# microInv_batt_controller.net
KiCad netlist of a schematic drawn in Altium Designer
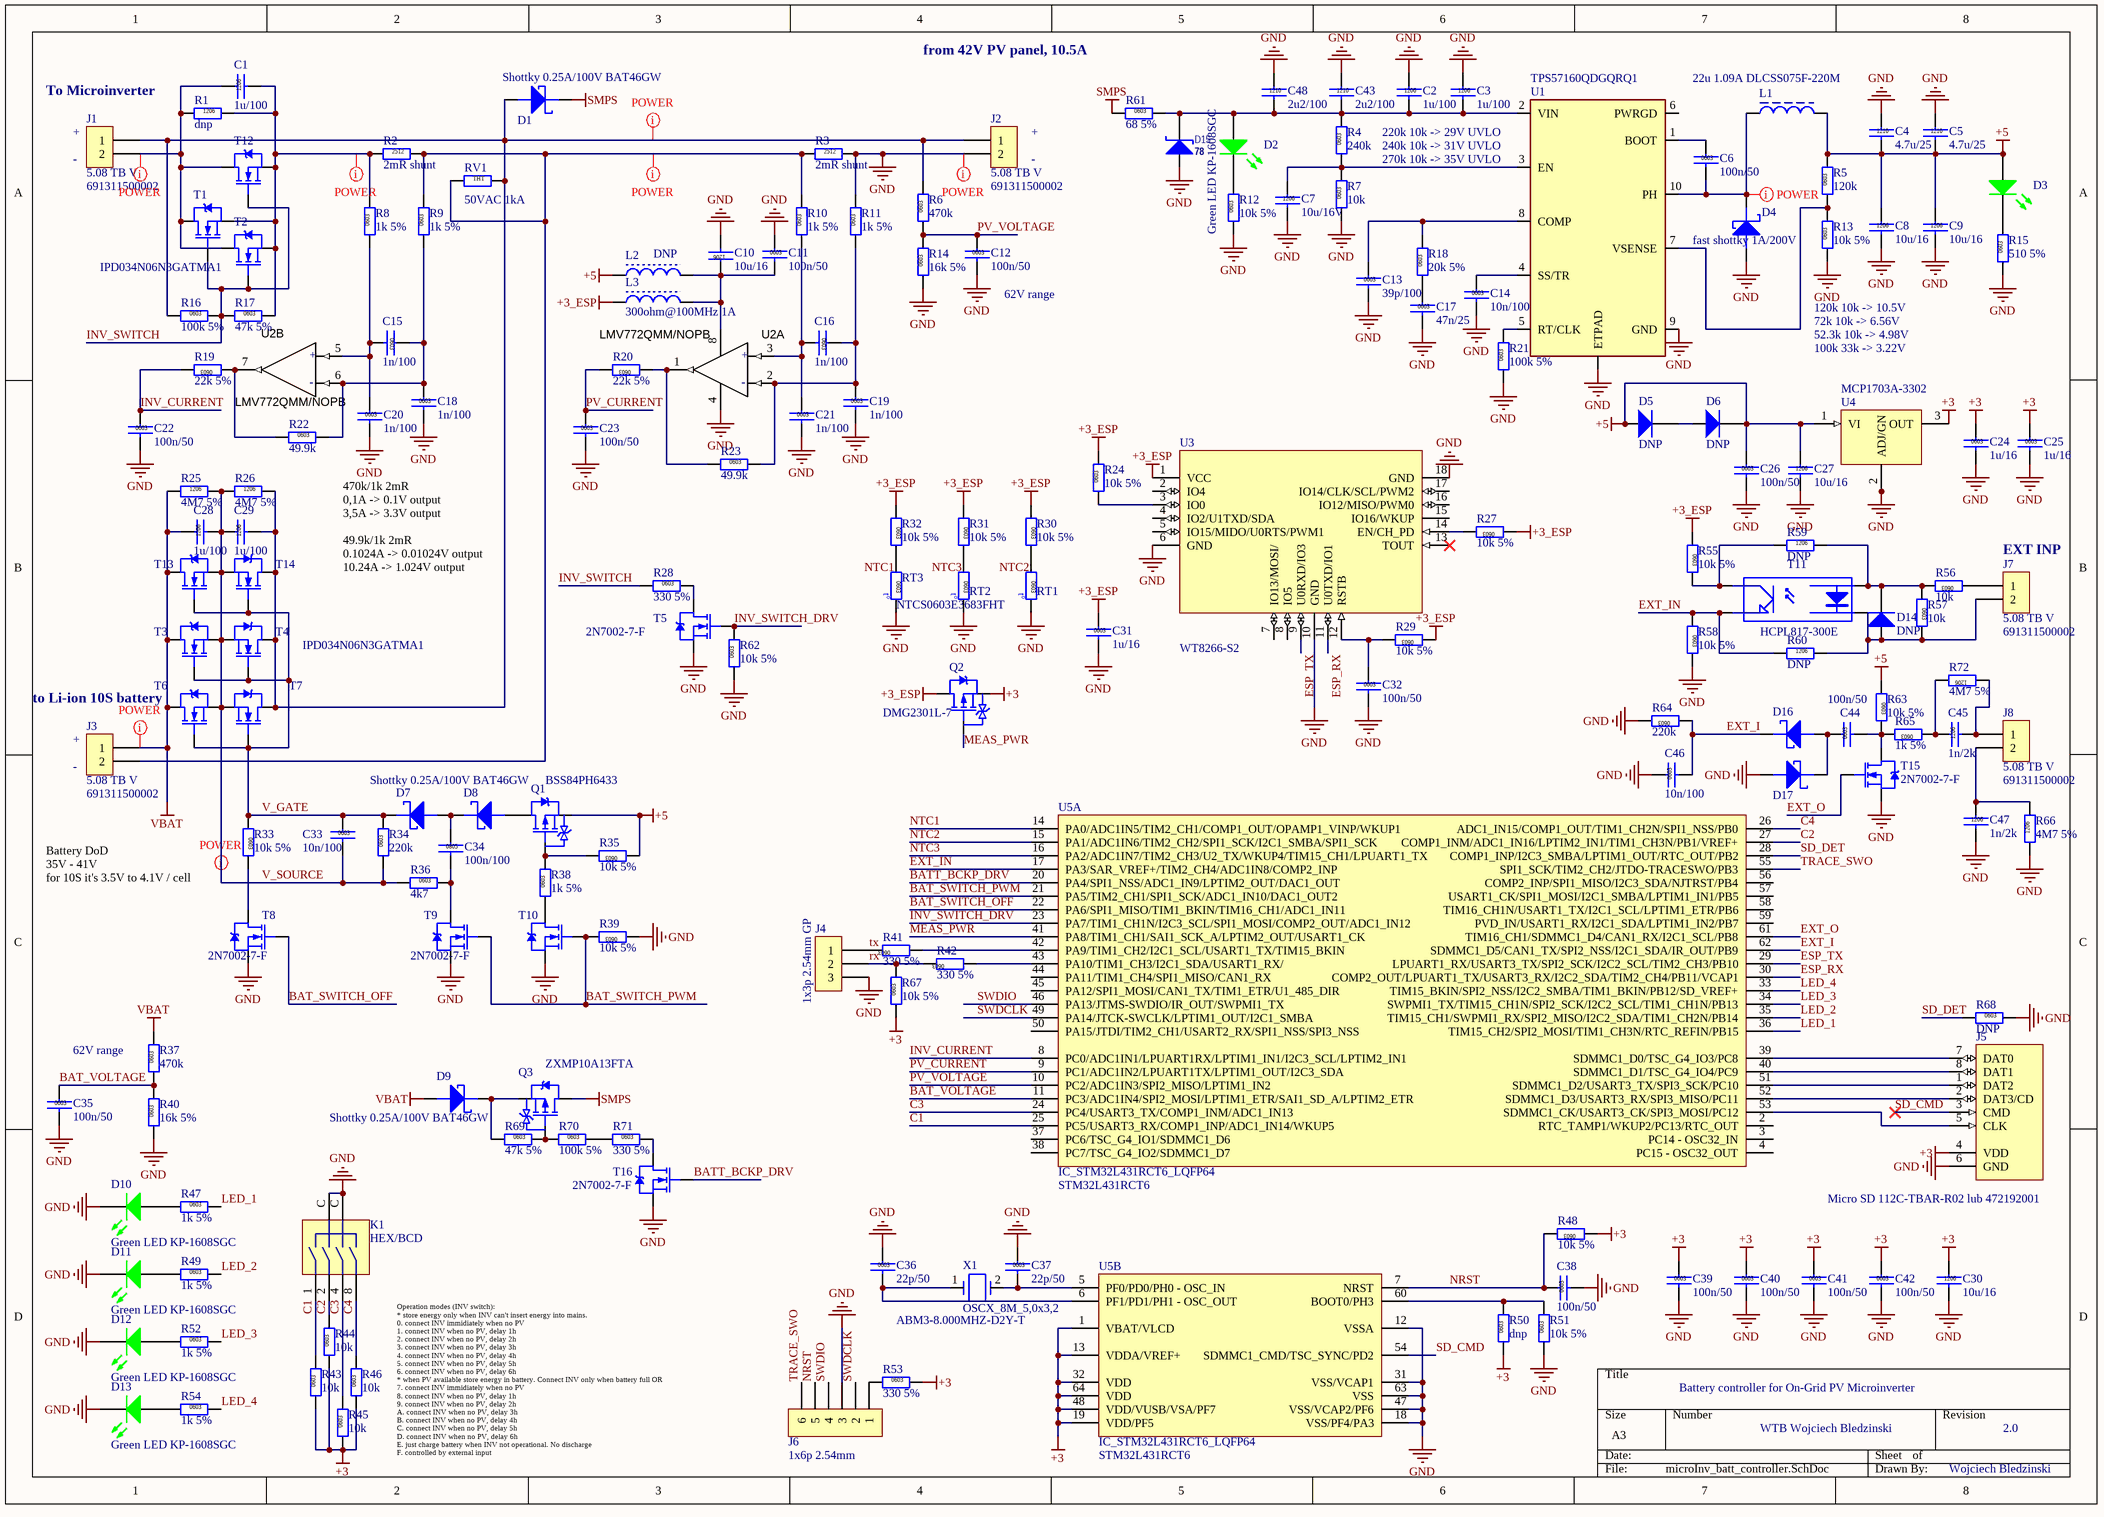
[diagram p0: microInv_batt_controller.SchDoc]

(export (version "E")
  (design (tool "Eeschema 10.0.6"))
  (components
    (comp (ref "C1")
      (value "1u/100")
      (footprint "CAP_1206")
      (description "X7R chip capacitor")
      (fields (field (name "MANUFACTURER") "AVX") (field (name "MANUFACTURER PART NUMBER") "12061C105KAT2A"))
      (libsource (lib "WB") (part "CAP_B_1u_100_1206_X7R"))
    )
    (comp (ref "C2")
      (value "1u/100")
      (footprint "CAP_1206")
      (description "X7R chip capacitor")
      (fields (field (name "MANUFACTURER") "AVX") (field (name "MANUFACTURER PART NUMBER") "12061C105KAT2A"))
      (libsource (lib "WB") (part "CAP_B_1u_100_1206_X7R"))
    )
    (comp (ref "C3")
      (value "1u/100")
      (footprint "CAP_1206")
      (description "X7R chip capacitor")
      (fields (field (name "MANUFACTURER") "AVX") (field (name "MANUFACTURER PART NUMBER") "12061C105KAT2A"))
      (libsource (lib "WB") (part "CAP_B_1u_100_1206_X7R"))
    )
    (comp (ref "C4")
      (value "4.7u/25")
      (footprint "CAP_1210")
      (description "X5R chip capacitor")
      (fields
        (field (name "MANUFACTURER") "YAGEO")
        (field (name "MANUFACTURER PART NUMBER") "CC1210KKX5R8BB475")
      )
      (libsource (lib "WB") (part "CAP_B_4.7u_25_1210_X5R"))
    )
    (comp (ref "C5")
      (value "4.7u/25")
      (footprint "CAP_1210")
      (description "X5R chip capacitor")
      (fields
        (field (name "MANUFACTURER") "YAGEO")
        (field (name "MANUFACTURER PART NUMBER") "CC1210KKX5R8BB475")
      )
      (libsource (lib "WB") (part "CAP_B_4.7u_25_1210_X5R"))
    )
    (comp (ref "C6")
      (value "100n/50")
      (footprint "CAP_0603")
      (description "X7R chip capacitor")
      (fields
        (field (name "MANUFACTURER") "SAMSUNG")
        (field (name "MANUFACTURER PART NUMBER") "CL10B104KB8NNNC")
      )
      (libsource (lib "WB") (part "CAP_B_100n_50_0603_X7R"))
    )
    (comp (ref "C7")
      (value "10u/16V")
      (footprint "CAP_1206")
      (description "X5R chip capacitor")
      (fields
        (field (name "MANUFACTURER") "SAMSUNG")
        (field (name "MANUFACTURER PART NUMBER") "CL31A106KAHNNNE")
      )
      (libsource (lib "WB") (part "CAP_B_10u_25_1206_X5R"))
    )
    (comp (ref "C8")
      (value "10u/16")
      (footprint "CAP_1206")
      (description "X7R chip capacitor")
      (fields
        (field (name "MANUFACTURER") "KYOCERA")
        (field (name "MANUFACTURER PART NUMBER") "CM316X7R106K16AT")
      )
      (libsource (lib "WB") (part "CAP_B_10u_16_1206_X7R"))
    )
    (comp (ref "C9")
      (value "10u/16")
      (footprint "CAP_1206")
      (description "X7R chip capacitor")
      (fields
        (field (name "MANUFACTURER") "KYOCERA")
        (field (name "MANUFACTURER PART NUMBER") "CM316X7R106K16AT")
      )
      (libsource (lib "WB") (part "CAP_B_10u_16_1206_X7R"))
    )
    (comp (ref "C10")
      (value "10u/16")
      (footprint "CAP_1206")
      (description "X7R chip capacitor")
      (fields
        (field (name "MANUFACTURER") "KYOCERA")
        (field (name "MANUFACTURER PART NUMBER") "CM316X7R106K16AT")
      )
      (libsource (lib "WB") (part "CAP_B_10u_16_1206_X7R"))
    )
    (comp (ref "C11")
      (value "100n/50")
      (footprint "CAP_0603")
      (description "X7R chip capacitor")
      (fields
        (field (name "MANUFACTURER") "SAMSUNG")
        (field (name "MANUFACTURER PART NUMBER") "CL10B104KB8NNNC")
      )
      (libsource (lib "WB") (part "CAP_B_100n_50_0603_X7R"))
    )
    (comp (ref "C12")
      (value "100n/50")
      (footprint "CAP_0603")
      (description "X7R chip capacitor")
      (fields
        (field (name "MANUFACTURER") "SAMSUNG")
        (field (name "MANUFACTURER PART NUMBER") "CL10B104KB8NNNC")
      )
      (libsource (lib "WB") (part "CAP_B_100n_50_0603_X7R"))
    )
    (comp (ref "C13")
      (value "39p/100")
      (footprint "CAP_0603")
      (description "COG chip capacitor")
      (fields (field (name "TOLERANCE") "10%") (field (name "VOLTAGE") "100"))
      (libsource (lib "WB") (part "CAP_B_39p_100_0603_COG"))
    )
    (comp (ref "C14")
      (value "10n/100")
      (footprint "CAP_0603")
      (description "X7R chip capacitor")
      (fields
        (field (name "MANUFACTURER") "SAMSUNG")
        (field (name "MANUFACTURER PART NUMBER") "CL10B103KC8NNNC")
      )
      (libsource (lib "WB") (part "CAP_B_10n_100_0603_X7R"))
    )
    (comp (ref "C15")
      (value "1n/100")
      (footprint "CAP_0603")
      (description "X7R chip capacitor")
      (fields
        (field (name "MANUFACTURER") "SAMSUNG")
        (field (name "MANUFACTURER PART NUMBER") "CL10B102KC8NNNC")
      )
      (libsource (lib "WB") (part "CAP_B_1n_100_0603_X7R"))
    )
    (comp (ref "C16")
      (value "1n/100")
      (footprint "CAP_0603")
      (description "X7R chip capacitor")
      (fields
        (field (name "MANUFACTURER") "SAMSUNG")
        (field (name "MANUFACTURER PART NUMBER") "CL10B102KC8NNNC")
      )
      (libsource (lib "WB") (part "CAP_B_1n_100_0603_X7R"))
    )
    (comp (ref "C17")
      (value "47n/25")
      (footprint "CAP_0603")
      (description "X7R chip capacitor")
      (fields (field (name "TOLERANCE") "10%") (field (name "VOLTAGE") "25"))
      (libsource (lib "WB") (part "CAP_B_47n_25_0603_X7R"))
    )
    (comp (ref "C18")
      (value "1n/100")
      (footprint "CAP_0603")
      (description "X7R chip capacitor")
      (fields
        (field (name "MANUFACTURER") "SAMSUNG")
        (field (name "MANUFACTURER PART NUMBER") "CL10B102KC8NNNC")
      )
      (libsource (lib "WB") (part "CAP_B_1n_100_0603_X7R"))
    )
    (comp (ref "C19")
      (value "1n/100")
      (footprint "CAP_0603")
      (description "X7R chip capacitor")
      (fields
        (field (name "MANUFACTURER") "SAMSUNG")
        (field (name "MANUFACTURER PART NUMBER") "CL10B102KC8NNNC")
      )
      (libsource (lib "WB") (part "CAP_B_1n_100_0603_X7R"))
    )
    (comp (ref "C20")
      (value "1n/100")
      (footprint "CAP_0603")
      (description "X7R chip capacitor")
      (fields
        (field (name "MANUFACTURER") "SAMSUNG")
        (field (name "MANUFACTURER PART NUMBER") "CL10B102KC8NNNC")
      )
      (libsource (lib "WB") (part "CAP_B_1n_100_0603_X7R"))
    )
    (comp (ref "C21")
      (value "1n/100")
      (footprint "CAP_0603")
      (description "X7R chip capacitor")
      (fields
        (field (name "MANUFACTURER") "SAMSUNG")
        (field (name "MANUFACTURER PART NUMBER") "CL10B102KC8NNNC")
      )
      (libsource (lib "WB") (part "CAP_B_1n_100_0603_X7R"))
    )
    (comp (ref "C22")
      (value "100n/50")
      (footprint "CAP_0603")
      (description "X7R chip capacitor")
      (fields
        (field (name "MANUFACTURER") "SAMSUNG")
        (field (name "MANUFACTURER PART NUMBER") "CL10B104KB8NNNC")
      )
      (libsource (lib "WB") (part "CAP_B_100n_50_0603_X7R"))
    )
    (comp (ref "C23")
      (value "100n/50")
      (footprint "CAP_0603")
      (description "X7R chip capacitor")
      (fields
        (field (name "MANUFACTURER") "SAMSUNG")
        (field (name "MANUFACTURER PART NUMBER") "CL10B104KB8NNNC")
      )
      (libsource (lib "WB") (part "CAP_B_100n_50_0603_X7R"))
    )
    (comp (ref "C24")
      (value "1u/16")
      (footprint "CAP_0603")
      (description "X7R chip capacitor")
      (fields
        (field (name "MANUFACTURER") "SAMSUNG")
        (field (name "MANUFACTURER PART NUMBER") "CL10B105KO8NNNC")
      )
      (libsource (lib "WB") (part "CAP_B_1u_16_0603_X7R"))
    )
    (comp (ref "C25")
      (value "1u/16")
      (footprint "CAP_0603")
      (description "X7R chip capacitor")
      (fields
        (field (name "MANUFACTURER") "SAMSUNG")
        (field (name "MANUFACTURER PART NUMBER") "CL10B105KO8NNNC")
      )
      (libsource (lib "WB") (part "CAP_B_1u_16_0603_X7R"))
    )
    (comp (ref "C26")
      (value "100n/50")
      (footprint "CAP_0603")
      (description "X7R chip capacitor")
      (fields
        (field (name "MANUFACTURER") "SAMSUNG")
        (field (name "MANUFACTURER PART NUMBER") "CL10B104KB8NNNC")
      )
      (libsource (lib "WB") (part "CAP_B_100n_50_0603_X7R"))
    )
    (comp (ref "C27")
      (value "10u/16")
      (footprint "CAP_1206")
      (description "X7R chip capacitor")
      (fields
        (field (name "MANUFACTURER") "KYOCERA")
        (field (name "MANUFACTURER PART NUMBER") "CM316X7R106K16AT")
      )
      (libsource (lib "WB") (part "CAP_B_10u_16_1206_X7R"))
    )
    (comp (ref "C28")
      (value "1u/100")
      (footprint "CAP_1206")
      (description "X7R chip capacitor")
      (fields (field (name "MANUFACTURER") "AVX") (field (name "MANUFACTURER PART NUMBER") "12061C105KAT2A"))
      (libsource (lib "WB") (part "CAP_B_1u_100_1206_X7R"))
    )
    (comp (ref "C29")
      (value "1u/100")
      (footprint "CAP_1206")
      (description "X7R chip capacitor")
      (fields (field (name "MANUFACTURER") "AVX") (field (name "MANUFACTURER PART NUMBER") "12061C105KAT2A"))
      (libsource (lib "WB") (part "CAP_B_1u_100_1206_X7R"))
    )
    (comp (ref "C30")
      (value "10u/16")
      (footprint "CAP_1206")
      (description "X7R chip capacitor")
      (fields
        (field (name "MANUFACTURER") "KYOCERA")
        (field (name "MANUFACTURER PART NUMBER") "CM316X7R106K16AT")
      )
      (libsource (lib "WB") (part "CAP_B_10u_16_1206_X7R"))
    )
    (comp (ref "C31")
      (value "1u/16")
      (footprint "CAP_0603")
      (description "X7R chip capacitor")
      (fields
        (field (name "MANUFACTURER") "SAMSUNG")
        (field (name "MANUFACTURER PART NUMBER") "CL10B105KO8NNNC")
      )
      (libsource (lib "WB") (part "CAP_B_1u_16_0603_X7R"))
    )
    (comp (ref "C32")
      (value "100n/50")
      (footprint "CAP_0603")
      (description "X7R chip capacitor")
      (fields
        (field (name "MANUFACTURER") "SAMSUNG")
        (field (name "MANUFACTURER PART NUMBER") "CL10B104KB8NNNC")
      )
      (libsource (lib "WB") (part "CAP_B_100n_50_0603_X7R"))
    )
    (comp (ref "C33")
      (value "10n/100")
      (footprint "CAP_0603")
      (description "X7R chip capacitor")
      (fields
        (field (name "MANUFACTURER") "SAMSUNG")
        (field (name "MANUFACTURER PART NUMBER") "CL10B103KC8NNNC")
      )
      (libsource (lib "WB") (part "CAP_B_10n_100_0603_X7R"))
    )
    (comp (ref "C34")
      (value "100n/100")
      (footprint "CAP_0805")
      (description "X7R chip capacitor")
      (fields (field (name "MANUFACTURER") "AVX") (field (name "MANUFACTURER PART NUMBER") "08051C104KAZ2A"))
      (libsource (lib "WB") (part "CAP_B_100n_100_0805_X7R"))
    )
    (comp (ref "C35")
      (value "100n/50")
      (footprint "CAP_0603")
      (description "X7R chip capacitor")
      (fields
        (field (name "MANUFACTURER") "SAMSUNG")
        (field (name "MANUFACTURER PART NUMBER") "CL10B104KB8NNNC")
      )
      (libsource (lib "WB") (part "CAP_B_100n_50_0603_X7R"))
    )
    (comp (ref "C36")
      (value "22p/50")
      (footprint "CAP_0603")
      (description "X7R chip capacitor")
      (fields (field (name "TOLERANCE") "10%") (field (name "VOLTAGE") "50"))
      (libsource (lib "WB") (part "CAP_B_22p_50_0603_X7R"))
    )
    (comp (ref "C37")
      (value "22p/50")
      (footprint "CAP_0603")
      (description "X7R chip capacitor")
      (fields (field (name "TOLERANCE") "10%") (field (name "VOLTAGE") "50"))
      (libsource (lib "WB") (part "CAP_B_22p_50_0603_X7R"))
    )
    (comp (ref "C38")
      (value "100n/50")
      (footprint "CAP_0603")
      (description "X7R chip capacitor")
      (fields
        (field (name "MANUFACTURER") "SAMSUNG")
        (field (name "MANUFACTURER PART NUMBER") "CL10B104KB8NNNC")
      )
      (libsource (lib "WB") (part "CAP_B_100n_50_0603_X7R"))
    )
    (comp (ref "C39")
      (value "100n/50")
      (footprint "CAP_0603")
      (description "X7R chip capacitor")
      (fields
        (field (name "MANUFACTURER") "SAMSUNG")
        (field (name "MANUFACTURER PART NUMBER") "CL10B104KB8NNNC")
      )
      (libsource (lib "WB") (part "CAP_B_100n_50_0603_X7R"))
    )
    (comp (ref "C40")
      (value "100n/50")
      (footprint "CAP_0603")
      (description "X7R chip capacitor")
      (fields
        (field (name "MANUFACTURER") "SAMSUNG")
        (field (name "MANUFACTURER PART NUMBER") "CL10B104KB8NNNC")
      )
      (libsource (lib "WB") (part "CAP_B_100n_50_0603_X7R"))
    )
    (comp (ref "C41")
      (value "100n/50")
      (footprint "CAP_0603")
      (description "X7R chip capacitor")
      (fields
        (field (name "MANUFACTURER") "SAMSUNG")
        (field (name "MANUFACTURER PART NUMBER") "CL10B104KB8NNNC")
      )
      (libsource (lib "WB") (part "CAP_B_100n_50_0603_X7R"))
    )
    (comp (ref "C42")
      (value "100n/50")
      (footprint "CAP_0603")
      (description "X7R chip capacitor")
      (fields
        (field (name "MANUFACTURER") "SAMSUNG")
        (field (name "MANUFACTURER PART NUMBER") "CL10B104KB8NNNC")
      )
      (libsource (lib "WB") (part "CAP_B_100n_50_0603_X7R"))
    )
    (comp (ref "C43")
      (value "2u2/100")
      (footprint "CAP_1210")
      (description "X7R chip capacitor")
      (fields
        (field (name "MANUFACTURER") "KEMET")
        (field (name "MANUFACTURER PART NUMBER") "C1210C225M1RACTU")
      )
      (libsource (lib "WB") (part "CAP_B_2u2_100_1210_X7R"))
    )
    (comp (ref "C44")
      (value "100n/50")
      (footprint "CAP_0603")
      (description "X7R chip capacitor")
      (fields
        (field (name "MANUFACTURER") "SAMSUNG")
        (field (name "MANUFACTURER PART NUMBER") "CL10B104KB8NNNC")
      )
      (libsource (lib "WB") (part "CAP_B_100n_50_0603_X7R"))
    )
    (comp (ref "C45")
      (value "1n/2k")
      (footprint "CAP_1206")
      (description "X7R chip capacitor")
      (fields
        (field (name "MANUFACTURER") "MULTICOMP")
        (field (name "MANUFACTURER PART NUMBER") "MC1206B102K202CT")
      )
      (libsource (lib "WB") (part "CAP_B_1n_2k_1206_X7R"))
    )
    (comp (ref "C46")
      (value "10n/100")
      (footprint "CAP_0603")
      (description "X7R chip capacitor")
      (fields
        (field (name "MANUFACTURER") "SAMSUNG")
        (field (name "MANUFACTURER PART NUMBER") "CL10B103KC8NNNC")
      )
      (libsource (lib "WB") (part "CAP_B_10n_100_0603_X7R"))
    )
    (comp (ref "C47")
      (value "1n/2k")
      (footprint "CAP_1206")
      (description "X7R chip capacitor")
      (fields
        (field (name "MANUFACTURER") "MULTICOMP")
        (field (name "MANUFACTURER PART NUMBER") "MC1206B102K202CT")
      )
      (libsource (lib "WB") (part "CAP_B_1n_2k_1206_X7R"))
    )
    (comp (ref "C48")
      (value "2u2/100")
      (footprint "CAP_1210")
      (description "X7R chip capacitor")
      (fields
        (field (name "MANUFACTURER") "KEMET")
        (field (name "MANUFACTURER PART NUMBER") "C1210C225M1RACTU")
      )
      (libsource (lib "WB") (part "CAP_B_2u2_100_1210_X7R"))
    )
    (comp (ref "D1")
      (value "Shottky 0.25A/100V BAT46GW")
      (footprint "SOD_123")
      (description "Shottky Diode trr 4ns 0,43V @ 0.05A 0.75V@0.25A")
      (fields
        (field (name "MANUFACTURER") "Nexperia")
        (field (name "MANUFACTURER PART NUMBER") "BAT46GWX 934070363115")
      )
      (libsource (lib "WB") (part "D_0.25_100_BAT46GWX"))
    )
    (comp (ref "D2")
      (value "Green LED KP-1608SGC")
      (footprint "LED_0603_GREEN")
      (description "Diode LED SMD 2.2V @ 20mA 15mcd")
      (fields
        (field (name "MANUFACTURER") "KINGBRIGHT")
        (field (name "MANUFACTURER PART NUMBER") "KP-1608SGC")
      )
      (libsource (lib "WB") (part "D_LED_0603_GREEN"))
    )
    (comp (ref "D3")
      (value "Green LED KP-1608SGC")
      (footprint "LED_0603_GREEN")
      (description "Diode LED SMD 2.2V @ 20mA 15mcd")
      (fields
        (field (name "MANUFACTURER") "KINGBRIGHT")
        (field (name "MANUFACTURER PART NUMBER") "KP-1608SGC")
      )
      (libsource (lib "WB") (part "D_LED_0603_GREEN"))
    )
    (comp (ref "D4")
      (value "fast shottky 1A/200V")
      (footprint "SMA_DO-214AC")
      (description "Shottky Diode 0,9V @ 1A trr=15ns 7pF")
      (fields (field (name "MANUFACTURER") "FAIRCHILD") (field (name "MANUFACTURER PART NUMBER") "ES1D"))
      (libsource (lib "WB") (part "D_1A_200_ES1D"))
    )
    (comp (ref "D5")
      (value "DNP")
      (footprint "D_MINIMELF")
      (fields
        (field (name "MANUFACTURER") "ON SEMICONDUCTOR (FAIRCHILD)")
        (field (name "MANUFACTURER PART NUMBER") "FDLL4148")
      )
      (libsource (lib "WB") (part "D_LL4148_MMELF"))
    )
    (comp (ref "D6")
      (value "DNP")
      (footprint "D_MINIMELF")
      (fields
        (field (name "MANUFACTURER") "ON SEMICONDUCTOR (FAIRCHILD)")
        (field (name "MANUFACTURER PART NUMBER") "FDLL4148")
      )
      (libsource (lib "WB") (part "D_LL4148_MMELF"))
    )
    (comp (ref "D7")
      (value "Shottky 0.25A/100V BAT46GW")
      (footprint "SOD_123")
      (description "Shottky Diode trr 4ns 0,43V @ 0.05A 0.75V@0.25A")
      (fields
        (field (name "MANUFACTURER") "Nexperia")
        (field (name "MANUFACTURER PART NUMBER") "BAT46GWX 934070363115")
      )
      (libsource (lib "WB") (part "D_0.25_100_BAT46GWX"))
    )
    (comp (ref "D8")
      (value "Shottky 0.25A/100V BAT46GW")
      (footprint "SOD_123")
      (description "Shottky Diode trr 4ns 0,43V @ 0.05A 0.75V@0.25A")
      (fields
        (field (name "MANUFACTURER") "Nexperia")
        (field (name "MANUFACTURER PART NUMBER") "BAT46GWX 934070363115")
      )
      (libsource (lib "WB") (part "D_0.25_100_BAT46GWX"))
    )
    (comp (ref "D9")
      (value "Shottky 0.25A/100V BAT46GW")
      (footprint "SOD_123")
      (description "Shottky Diode trr 4ns 0,43V @ 0.05A 0.75V@0.25A")
      (fields
        (field (name "MANUFACTURER") "Nexperia")
        (field (name "MANUFACTURER PART NUMBER") "BAT46GWX 934070363115")
      )
      (libsource (lib "WB") (part "D_0.25_100_BAT46GWX"))
    )
    (comp (ref "D10")
      (value "Green LED KP-1608SGC")
      (footprint "LED_0603_GREEN")
      (description "Diode LED SMD 2.2V @ 20mA 15mcd")
      (fields
        (field (name "MANUFACTURER") "KINGBRIGHT")
        (field (name "MANUFACTURER PART NUMBER") "KP-1608SGC")
      )
      (libsource (lib "WB") (part "D_LED_0603_GREEN"))
    )
    (comp (ref "D11")
      (value "Green LED KP-1608SGC")
      (footprint "LED_0603_GREEN")
      (description "Diode LED SMD 2.2V @ 20mA 15mcd")
      (fields
        (field (name "MANUFACTURER") "KINGBRIGHT")
        (field (name "MANUFACTURER PART NUMBER") "KP-1608SGC")
      )
      (libsource (lib "WB") (part "D_LED_0603_GREEN"))
    )
    (comp (ref "D12")
      (value "Green LED KP-1608SGC")
      (footprint "LED_0603_GREEN")
      (description "Diode LED SMD 2.2V @ 20mA 15mcd")
      (fields
        (field (name "MANUFACTURER") "KINGBRIGHT")
        (field (name "MANUFACTURER PART NUMBER") "KP-1608SGC")
      )
      (libsource (lib "WB") (part "D_LED_0603_GREEN"))
    )
    (comp (ref "D13")
      (value "Green LED KP-1608SGC")
      (footprint "LED_0603_GREEN")
      (description "Diode LED SMD 2.2V @ 20mA 15mcd")
      (fields
        (field (name "MANUFACTURER") "KINGBRIGHT")
        (field (name "MANUFACTURER PART NUMBER") "KP-1608SGC")
      )
      (libsource (lib "WB") (part "D_LED_0603_GREEN"))
    )
    (comp (ref "D14")
      (value "DNP")
      (footprint "D_MINIMELF")
      (fields
        (field (name "MANUFACTURER") "ON SEMICONDUCTOR (FAIRCHILD)")
        (field (name "MANUFACTURER PART NUMBER") "FDLL4148")
      )
      (libsource (lib "WB") (part "D_LL4148_MMELF"))
    )
    (comp (ref "D15")
      (value "78")
      (footprint "SMA_DO-214AC")
      (description "transil jednostronny 400W")
      (fields (field (name "MANUFACTURER") "MULTICOMP") (field (name "MANUFACTURER PART NUMBER") "SMAJ78A"))
      (libsource (lib "WB") (part "D_TR_UNI_SMAJ78A"))
    )
    (comp (ref "D16")
      (value "Shottky 0.25A/100V BAT46GW")
      (footprint "SOD_123")
      (description "Shottky Diode trr 4ns 0,43V @ 0.05A 0.75V@0.25A")
      (fields
        (field (name "MANUFACTURER") "Nexperia")
        (field (name "MANUFACTURER PART NUMBER") "BAT46GWX 934070363115")
      )
      (libsource (lib "WB") (part "D_0.25_100_BAT46GWX"))
    )
    (comp (ref "D17")
      (value "Shottky 0.25A/100V BAT46GW")
      (footprint "SOD_123")
      (description "Shottky Diode trr 4ns 0,43V @ 0.05A 0.75V@0.25A")
      (fields
        (field (name "MANUFACTURER") "Nexperia")
        (field (name "MANUFACTURER PART NUMBER") "BAT46GWX 934070363115")
      )
      (libsource (lib "WB") (part "D_0.25_100_BAT46GWX"))
    )
    (comp (ref "J1")
      (value "5.08 TB V")
      (footprint "CON_1x2_5.08TB")
      (description "THT 5,08mm, WE 691311500002 (rev1), NINIGI , MLX")
      (fields
        (field (name "MANUFACTURER") "Wurth Electronics")
        (field (name "MANUFACTURER PART NUMBER") "691311500002")
      )
      (libsource (lib "WB") (part "CON_1x2_TB_5.08V"))
    )
    (comp (ref "J2")
      (value "5.08 TB V")
      (footprint "CON_1x2_5.08TB")
      (description "THT 5,08mm, WE 691311500002 (rev1), NINIGI , MLX")
      (fields
        (field (name "MANUFACTURER") "Wurth Electronics")
        (field (name "MANUFACTURER PART NUMBER") "691311500002")
      )
      (libsource (lib "") (part "CON_1x2_TB_5.08V_1"))
    )
    (comp (ref "J3")
      (value "5.08 TB V")
      (footprint "CON_1x2_5.08TB")
      (description "THT 5,08mm, WE 691311500002 (rev1), NINIGI , MLX")
      (fields
        (field (name "MANUFACTURER") "Wurth Electronics")
        (field (name "MANUFACTURER PART NUMBER") "691311500002")
      )
      (libsource (lib "WB") (part "CON_1x2_TB_5.08V"))
    )
    (comp (ref "J4")
      (value "1x3p 2.54mm GP")
      (footprint "CON_PIN1x3_THT")
      (description "THT 2,54 goldpin")
      (fields (field (name "MANUFACTURER") "TME") (field (name "MANUFACTURER PART NUMBER") "ZL201-03G"))
      (libsource (lib "WB") (part "CON_1x3_GP_THT"))
    )
    (comp (ref "J5")
      (value "Micro SD 112C-TBAR-R02 lub 472192001")
      (footprint "112C_TXAR_R01")
      (description "Micro SD connector SMD, ATTEND 112C-TBAR-R02; MOLEX 472192001")
      (fields
        (field (name "MANUFACTURER") "ATTEND")
        (field (name "MANUFACTURER PART NUMBER") "112C-TBAR-R02")
      )
      (libsource (lib "WB") (part "CON_MicroSD"))
    )
    (comp (ref "J6")
      (value "1x6p 2.54mm")
      (footprint "CON_PIN1x6_THT")
      (description "THT 2,54 goldpin")
      (fields
        (field (name "MANUFACTURER") "CONNFLY")
        (field (name "MANUFACTURER PART NUMBER") "DS1021-1*6SF1-1")
      )
      (libsource (lib "WB") (part "CON_1x6_GP_THT"))
    )
    (comp (ref "J7")
      (value "5.08 TB V")
      (footprint "CON_1x2_5.08TB")
      (description "THT 5,08mm, WE 691311500002 (rev1), NINIGI , MLX")
      (fields
        (field (name "MANUFACTURER") "Wurth Electronics")
        (field (name "MANUFACTURER PART NUMBER") "691311500002")
      )
      (libsource (lib "") (part "CON_1x2_TB_5.08V_1"))
    )
    (comp (ref "J8")
      (value "5.08 TB V")
      (footprint "CON_1x2_5.08TB")
      (description "THT 5,08mm, WE 691311500002 (rev1), NINIGI , MLX")
      (fields
        (field (name "MANUFACTURER") "Wurth Electronics")
        (field (name "MANUFACTURER PART NUMBER") "691311500002")
      )
      (libsource (lib "") (part "CON_1x2_TB_5.08V_1"))
    )
    (comp (ref "K1")
      (value "HEX/BCD")
      (footprint "MECH_SW_HEXBCD")
      (description "Zadajnik kodu")
      (fields (field (name "MANUFACTURER") "ECE") (field (name "MANUFACTURER PART NUMBER") "ERD116RSZ"))
      (libsource (lib "WB") (part "MECH_SW_HEXBCD"))
    )
    (comp (ref "L1")
      (value "22u 1.09A DLCSS075F-220M")
      (footprint "IND_DER0705")
      (description "shielded power inductor 1.09A Rdc=0,12")
      (fields
        (field (name "MANUFACTURER") "FERROCORE")
        (field (name "MANUFACTURER PART NUMBER") "DER0705-22")
      )
      (libsource (lib "WB") (part "IND_22u_1.09A_DER0705-22"))
    )
    (comp (ref "L2")
      (value "DNP")
      (footprint "RES_0603")
      (description "2A Rdc=0,15 SRF 250MHz")
      (fields (field (name "MANUFACTURER") "WE") (field (name "MANUFACTURER PART NUMBER") "742792641"))
      (libsource (lib "WB") (part "IND_FB_300R_0603"))
    )
    (comp (ref "L3")
      (value "300ohm@100MHz 1A")
      (footprint "RES_0603")
      (description "2A Rdc=0,15 SRF 250MHz")
      (fields (field (name "MANUFACTURER") "WE") (field (name "MANUFACTURER PART NUMBER") "742792641"))
      (libsource (lib "WB") (part "IND_FB_300R_0603"))
    )
    (comp (ref "Q1")
      (value "BSS84PH6433")
      (footprint "SOT23-3")
      (description "50V 130mA P Mosfet")
      (fields (field (name "MANUFACTURER") "INFINEON TECHNOLOGIES") (field (name "POWER") "360mW"))
      (libsource (lib "WB") (part "T_BSS84"))
    )
    (comp (ref "Q2")
      (value "DMG2301L-7")
      (footprint "SOT23-3")
      (description "20V 3A P Mosfet")
      (fields (field (name "MANUFACTURER") "DIODES"))
      (libsource (lib "WB") (part "T_DMG2301L-7"))
    )
    (comp (ref "Q3")
      (value "ZXMP10A13FTA")
      (footprint "SOT23-3")
      (description "100V 700mA P Mosfet")
      (fields (field (name "MANUFACTURER") "DIODES"))
      (libsource (lib "WB") (part "T_ZXMP10A13FTA"))
    )
    (comp (ref "R1")
      (value "dnp")
      (footprint "RES_1206")
      (description "Resistor 1206 5% 0,25W")
      (fields
        (field (name "MANUFACTURER") "ROYAL OHM")
        (field (name "MANUFACTURER PART NUMBER") "1206S4J0000T5E")
      )
      (libsource (lib "WB") (part "RES_0R_5p_1206"))
    )
    (comp (ref "R2")
      (value "2mR shunt")
      (footprint "RES_2512_shunt")
      (description "Resistor 2512 5% 1W")
      (fields (field (name "MANUFACTURER") "YAGEO") (field (name "TOLERANCE") "5%"))
      (libsource (lib "WB") (part "RES_2mR_1p_2512"))
    )
    (comp (ref "R3")
      (value "2mR shunt")
      (footprint "RES_2512_shunt")
      (description "Resistor 2512 5% 1W")
      (fields (field (name "MANUFACTURER") "YAGEO") (field (name "TOLERANCE") "5%"))
      (libsource (lib "WB") (part "RES_2mR_1p_2512"))
    )
    (comp (ref "R4")
      (value "240k")
      (footprint "RES_0603")
      (description "Resistor 0603 5% 0,1W")
      (fields (field (name "TOLERANCE") "5%") (field (name "VOLTAGE") "50"))
      (libsource (lib "WB") (part "RES_105k_5p_0603"))
    )
    (comp (ref "R5")
      (value "120k")
      (footprint "RES_0603")
      (description "Resistor 0603 5% 0,1W")
      (fields (field (name "MANUFACTURER") "YAGEO") (field (name "TOLERANCE") "5%"))
      (libsource (lib "WB") (part "RES_62k_5p_0603"))
    )
    (comp (ref "R6")
      (value "470k")
      (footprint "RES_0603")
      (description "Resistor 0603 5% 0,1W")
      (fields (field (name "MANUFACTURER") "YAGEO") (field (name "TOLERANCE") "5%"))
      (libsource (lib "") (part "RES_1k_5p_0603_2"))
    )
    (comp (ref "R7")
      (value "10k")
      (footprint "RES_0603")
      (description "Resistor 0603 5% 0,1W")
      (fields (field (name "MANUFACTURER") "YAGEO") (field (name "TOLERANCE") "5%"))
      (libsource (lib "WB") (part "RES_16k_5p_0603"))
    )
    (comp (ref "R8")
      (value "1k 5%")
      (footprint "RES_0603")
      (description "Resistor 0603 5% 0,1W")
      (fields (field (name "MANUFACTURER") "YAGEO") (field (name "TOLERANCE") "5%"))
      (libsource (lib "") (part "RES_1k_5p_0603_2"))
    )
    (comp (ref "R9")
      (value "1k 5%")
      (footprint "RES_0603")
      (description "Resistor 0603 5% 0,1W")
      (fields (field (name "MANUFACTURER") "YAGEO") (field (name "TOLERANCE") "5%"))
      (libsource (lib "") (part "RES_1k_5p_0603_2"))
    )
    (comp (ref "R10")
      (value "1k 5%")
      (footprint "RES_0603")
      (description "Resistor 0603 5% 0,1W")
      (fields (field (name "MANUFACTURER") "YAGEO") (field (name "TOLERANCE") "5%"))
      (libsource (lib "") (part "RES_1k_5p_0603_2"))
    )
    (comp (ref "R11")
      (value "1k 5%")
      (footprint "RES_0603")
      (description "Resistor 0603 5% 0,1W")
      (fields (field (name "MANUFACTURER") "YAGEO") (field (name "TOLERANCE") "5%"))
      (libsource (lib "") (part "RES_1k_5p_0603_2"))
    )
    (comp (ref "R12")
      (value "10k 5%")
      (footprint "RES_0603")
      (description "Resistor 0603 5% 0,1W")
      (fields (field (name "TOLERANCE") "5%") (field (name "VOLTAGE") "50"))
      (libsource (lib "WB") (part "RES_10k_5p_0603"))
    )
    (comp (ref "R13")
      (value "10k 5%")
      (footprint "RES_0603")
      (description "Resistor 0603 5% 0,1W")
      (fields (field (name "TOLERANCE") "5%") (field (name "VOLTAGE") "50"))
      (libsource (lib "WB") (part "RES_10k_5p_0603"))
    )
    (comp (ref "R14")
      (value "16k 5%")
      (footprint "RES_0603")
      (description "Resistor 0603 5% 0,1W")
      (fields (field (name "MANUFACTURER") "YAGEO") (field (name "TOLERANCE") "5%"))
      (libsource (lib "WB") (part "RES_16k_5p_0603"))
    )
    (comp (ref "R15")
      (value "510 5%")
      (footprint "RES_0603")
      (description "Resistor 0603 5% 0,1W")
      (fields (field (name "TOLERANCE") "5%") (field (name "VOLTAGE") "50"))
      (libsource (lib "WB") (part "RES_510_5p_0603"))
    )
    (comp (ref "R16")
      (value "100k 5%")
      (footprint "RES_0603")
      (description "Resistor 0603 5% 0,1W")
      (fields (field (name "TOLERANCE") "5%") (field (name "VOLTAGE") "50"))
      (libsource (lib "") (part "RES_100k_5p_0603_1"))
    )
    (comp (ref "R17")
      (value "47k 5%")
      (footprint "RES_0603")
      (description "Resistor 0603 5% 0,1W")
      (fields (field (name "MANUFACTURER") "YAGEO") (field (name "TOLERANCE") "5%"))
      (libsource (lib "WB") (part "RES_47k_5p_0603"))
    )
    (comp (ref "R18")
      (value "20k 5%")
      (footprint "RES_0603")
      (description "Resistor 0603 5% 0,1W")
      (fields
        (field (name "MANUFACTURER") "ROYAL OHM")
        (field (name "MANUFACTURER PART NUMBER") "0603SAJ0203T5E")
      )
      (libsource (lib "WB") (part "RES_20k_5p_0603"))
    )
    (comp (ref "R19")
      (value "22k 5%")
      (footprint "RES_0603")
      (description "Resistor 0603 5% 0,1W")
      (fields (field (name "MANUFACTURER") "YAGEO") (field (name "TOLERANCE") "5%"))
      (libsource (lib "WB") (part "RES_22k_5p_0603"))
    )
    (comp (ref "R20")
      (value "22k 5%")
      (footprint "RES_0603")
      (description "Resistor 0603 5% 0,1W")
      (fields (field (name "MANUFACTURER") "YAGEO") (field (name "TOLERANCE") "5%"))
      (libsource (lib "WB") (part "RES_22k_5p_0603"))
    )
    (comp (ref "R21")
      (value "100k 5%")
      (footprint "RES_0603")
      (description "Resistor 0603 5% 0,1W")
      (fields (field (name "TOLERANCE") "5%") (field (name "VOLTAGE") "50"))
      (libsource (lib "") (part "RES_100k_5p_0603_2"))
    )
    (comp (ref "R22")
      (value "49.9k")
      (footprint "RES_0603")
      (description "Resistor 0603 5% 0,1W")
      (fields (field (name "MANUFACTURER") "YAGEO") (field (name "TOLERANCE") "5%"))
      (libsource (lib "") (part "RES_1k_5p_0603_1"))
    )
    (comp (ref "R23")
      (value "49.9k")
      (footprint "RES_0603")
      (description "Resistor 0603 5% 0,1W")
      (fields (field (name "MANUFACTURER") "YAGEO") (field (name "TOLERANCE") "5%"))
      (libsource (lib "") (part "RES_1k_5p_0603_1"))
    )
    (comp (ref "R24")
      (value "10k 5%")
      (footprint "RES_0603")
      (description "Resistor 0603 5% 0,1W")
      (fields (field (name "TOLERANCE") "5%") (field (name "VOLTAGE") "50"))
      (libsource (lib "WB") (part "RES_10k_5p_0603"))
    )
    (comp (ref "R25")
      (value "4M7 5%")
      (footprint "RES_1206")
      (description "Resistor 1206 5% 0,25W")
      (fields
        (field (name "MANUFACTURER") "ROYAL OHM")
        (field (name "MANUFACTURER PART NUMBER") "1206S4J0475T5E")
      )
      (libsource (lib "WB") (part "RES_4M7_5p_1206"))
    )
    (comp (ref "R26")
      (value "4M7 5%")
      (footprint "RES_1206")
      (description "Resistor 1206 5% 0,25W")
      (fields
        (field (name "MANUFACTURER") "ROYAL OHM")
        (field (name "MANUFACTURER PART NUMBER") "1206S4J0475T5E")
      )
      (libsource (lib "WB") (part "RES_4M7_5p_1206"))
    )
    (comp (ref "R27")
      (value "10k 5%")
      (footprint "RES_0603")
      (description "Resistor 0603 5% 0,1W")
      (fields (field (name "TOLERANCE") "5%") (field (name "VOLTAGE") "50"))
      (libsource (lib "") (part "RES_10k_5p_0603_2"))
    )
    (comp (ref "R28")
      (value "330 5%")
      (footprint "RES_0603")
      (description "Resistor 0603 5% 0,1W")
      (fields (field (name "TOLERANCE") "5%") (field (name "VOLTAGE") "50"))
      (libsource (lib "WB") (part "RES_330R_5p_0603"))
    )
    (comp (ref "R29")
      (value "10k 5%")
      (footprint "RES_0603")
      (description "Resistor 0603 5% 0,1W")
      (fields (field (name "TOLERANCE") "5%") (field (name "VOLTAGE") "50"))
      (libsource (lib "") (part "RES_10k_5p_0603_2"))
    )
    (comp (ref "R30")
      (value "10k 5%")
      (footprint "RES_0603")
      (description "Resistor 0603 5% 0,1W")
      (fields (field (name "TOLERANCE") "5%") (field (name "VOLTAGE") "50"))
      (libsource (lib "") (part "RES_10k_5p_0603_1"))
    )
    (comp (ref "R31")
      (value "10k 5%")
      (footprint "RES_0603")
      (description "Resistor 0603 5% 0,1W")
      (fields (field (name "TOLERANCE") "5%") (field (name "VOLTAGE") "50"))
      (libsource (lib "") (part "RES_10k_5p_0603_1"))
    )
    (comp (ref "R32")
      (value "10k 5%")
      (footprint "RES_0603")
      (description "Resistor 0603 5% 0,1W")
      (fields (field (name "TOLERANCE") "5%") (field (name "VOLTAGE") "50"))
      (libsource (lib "") (part "RES_10k_5p_0603_1"))
    )
    (comp (ref "R33")
      (value "10k 5%")
      (footprint "RES_0603")
      (description "Resistor 0603 5% 0,1W")
      (fields (field (name "TOLERANCE") "5%") (field (name "VOLTAGE") "50"))
      (libsource (lib "") (part "RES_10k_5p_0603_1"))
    )
    (comp (ref "R34")
      (value "220k")
      (footprint "RES_0603")
      (description "Resistor 0603 5% 0,1W")
      (fields (field (name "TOLERANCE") "5%") (field (name "VOLTAGE") "50"))
      (libsource (lib "") (part "RES_100k_5p_0603_2"))
    )
    (comp (ref "R35")
      (value "10k 5%")
      (footprint "RES_0603")
      (description "Resistor 0603 5% 0,1W")
      (fields (field (name "TOLERANCE") "5%") (field (name "VOLTAGE") "50"))
      (libsource (lib "") (part "RES_10k_5p_0603_2"))
    )
    (comp (ref "R36")
      (value "4k7")
      (footprint "RES_0603")
      (description "Resistor 0603 5% 0,1W")
      (fields (field (name "TOLERANCE") "5%") (field (name "VOLTAGE") "50"))
      (libsource (lib "") (part "RES_100k_5p_0603_1"))
    )
    (comp (ref "R37")
      (value "470k")
      (footprint "RES_0603")
      (description "Resistor 0603 5% 0,1W")
      (fields (field (name "MANUFACTURER") "YAGEO") (field (name "TOLERANCE") "5%"))
      (libsource (lib "") (part "RES_1k_5p_0603_2"))
    )
    (comp (ref "R38")
      (value "1k 5%")
      (footprint "RES_0603")
      (description "Resistor 0603 5% 0,1W")
      (fields (field (name "MANUFACTURER") "YAGEO") (field (name "TOLERANCE") "5%"))
      (libsource (lib "") (part "RES_1k_5p_0603_2"))
    )
    (comp (ref "R39")
      (value "10k 5%")
      (footprint "RES_0603")
      (description "Resistor 0603 5% 0,1W")
      (fields (field (name "TOLERANCE") "5%") (field (name "VOLTAGE") "50"))
      (libsource (lib "") (part "RES_10k_5p_0603_2"))
    )
    (comp (ref "R40")
      (value "16k 5%")
      (footprint "RES_0603")
      (description "Resistor 0603 5% 0,1W")
      (fields (field (name "MANUFACTURER") "YAGEO") (field (name "TOLERANCE") "5%"))
      (libsource (lib "WB") (part "RES_16k_5p_0603"))
    )
    (comp (ref "R41")
      (value "330 5%")
      (footprint "RES_0603")
      (description "Resistor 0603 5% 0,1W")
      (fields (field (name "TOLERANCE") "5%") (field (name "VOLTAGE") "50"))
      (libsource (lib "") (part "RES_330R_5p_0603_1"))
    )
    (comp (ref "R42")
      (value "330 5%")
      (footprint "RES_0603")
      (description "Resistor 0603 5% 0,1W")
      (fields (field (name "TOLERANCE") "5%") (field (name "VOLTAGE") "50"))
      (libsource (lib "") (part "RES_330R_5p_0603_1"))
    )
    (comp (ref "R43")
      (value "10k")
      (footprint "RES_0603")
      (description "Resistor 0603 5% 0,1W")
      (fields (field (name "MANUFACTURER") "YAGEO") (field (name "TOLERANCE") "5%"))
      (libsource (lib "WB") (part "RES_16k_5p_0603"))
    )
    (comp (ref "R44")
      (value "10k")
      (footprint "RES_0603")
      (description "Resistor 0603 5% 0,1W")
      (fields (field (name "MANUFACTURER") "YAGEO") (field (name "TOLERANCE") "5%"))
      (libsource (lib "WB") (part "RES_16k_5p_0603"))
    )
    (comp (ref "R45")
      (value "10k")
      (footprint "RES_0603")
      (description "Resistor 0603 5% 0,1W")
      (fields (field (name "MANUFACTURER") "YAGEO") (field (name "TOLERANCE") "5%"))
      (libsource (lib "WB") (part "RES_16k_5p_0603"))
    )
    (comp (ref "R46")
      (value "10k")
      (footprint "RES_0603")
      (description "Resistor 0603 5% 0,1W")
      (fields (field (name "MANUFACTURER") "YAGEO") (field (name "TOLERANCE") "5%"))
      (libsource (lib "WB") (part "RES_16k_5p_0603"))
    )
    (comp (ref "R47")
      (value "1k 5%")
      (footprint "RES_0603")
      (description "Resistor 0603 5% 0,1W")
      (fields (field (name "MANUFACTURER") "YAGEO") (field (name "TOLERANCE") "5%"))
      (libsource (lib "") (part "RES_1k_5p_0603_1"))
    )
    (comp (ref "R48")
      (value "10k 5%")
      (footprint "RES_0603")
      (description "Resistor 0603 5% 0,1W")
      (fields (field (name "TOLERANCE") "5%") (field (name "VOLTAGE") "50"))
      (libsource (lib "") (part "RES_10k_5p_0603_2"))
    )
    (comp (ref "R49")
      (value "1k 5%")
      (footprint "RES_0603")
      (description "Resistor 0603 5% 0,1W")
      (fields (field (name "MANUFACTURER") "YAGEO") (field (name "TOLERANCE") "5%"))
      (libsource (lib "") (part "RES_1k_5p_0603_1"))
    )
    (comp (ref "R50")
      (value "dnp")
      (footprint "RES_0603")
      (description "Resistor 0603 5% 0,1W")
      (fields (field (name "TOLERANCE") "5%") (field (name "VOLTAGE") "50"))
      (libsource (lib "WB") (part "RES_10k_5p_0603"))
    )
    (comp (ref "R51")
      (value "10k 5%")
      (footprint "RES_0603")
      (description "Resistor 0603 5% 0,1W")
      (fields (field (name "TOLERANCE") "5%") (field (name "VOLTAGE") "50"))
      (libsource (lib "WB") (part "RES_10k_5p_0603"))
    )
    (comp (ref "R52")
      (value "1k 5%")
      (footprint "RES_0603")
      (description "Resistor 0603 5% 0,1W")
      (fields (field (name "MANUFACTURER") "YAGEO") (field (name "TOLERANCE") "5%"))
      (libsource (lib "") (part "RES_1k_5p_0603_1"))
    )
    (comp (ref "R53")
      (value "330 5%")
      (footprint "RES_0603")
      (description "Resistor 0603 5% 0,1W")
      (fields (field (name "TOLERANCE") "5%") (field (name "VOLTAGE") "50"))
      (libsource (lib "WB") (part "RES_330R_5p_0603"))
    )
    (comp (ref "R54")
      (value "1k 5%")
      (footprint "RES_0603")
      (description "Resistor 0603 5% 0,1W")
      (fields (field (name "MANUFACTURER") "YAGEO") (field (name "TOLERANCE") "5%"))
      (libsource (lib "") (part "RES_1k_5p_0603_1"))
    )
    (comp (ref "R55")
      (value "10k 5%")
      (footprint "RES_0603")
      (description "Resistor 0603 5% 0,1W")
      (fields (field (name "TOLERANCE") "5%") (field (name "VOLTAGE") "50"))
      (libsource (lib "") (part "RES_10k_5p_0603_1"))
    )
    (comp (ref "R56")
      (value "10k")
      (footprint "RES_0603")
      (description "Resistor 0603 5% 0,1W")
      (fields (field (name "MANUFACTURER") "YAGEO") (field (name "TOLERANCE") "5%"))
      (libsource (lib "") (part "RES_16k_5p_0603_1"))
    )
    (comp (ref "R57")
      (value "10k")
      (footprint "RES_0603")
      (description "Resistor 0603 5% 0,1W")
      (fields (field (name "MANUFACTURER") "YAGEO") (field (name "TOLERANCE") "5%"))
      (libsource (lib "") (part "RES_16k_5p_0603_2"))
    )
    (comp (ref "R58")
      (value "10k 5%")
      (footprint "RES_0603")
      (description "Resistor 0603 5% 0,1W")
      (fields (field (name "TOLERANCE") "5%") (field (name "VOLTAGE") "50"))
      (libsource (lib "") (part "RES_10k_5p_0603_1"))
    )
    (comp (ref "R59")
      (value "DNP")
      (footprint "RES_1206")
      (description "Resistor 1206 5% 0,25W")
      (fields
        (field (name "MANUFACTURER") "ROYAL OHM")
        (field (name "MANUFACTURER PART NUMBER") "1206S4J0000T5E")
      )
      (libsource (lib "WB") (part "RES_0R_5p_1206"))
    )
    (comp (ref "R60")
      (value "DNP")
      (footprint "RES_1206")
      (description "Resistor 1206 5% 0,25W")
      (fields
        (field (name "MANUFACTURER") "ROYAL OHM")
        (field (name "MANUFACTURER PART NUMBER") "1206S4J0000T5E")
      )
      (libsource (lib "WB") (part "RES_0R_5p_1206"))
    )
    (comp (ref "R61")
      (value "68 5%")
      (footprint "RES_0603")
      (description "0603 ,1W")
      (fields
        (field (name "MANUFACTURER") "ROYAL OHM")
        (field (name "MANUFACTURER PART NUMBER") "0603SAJ0680T5E")
      )
      (libsource (lib "WB") (part "RES_68_5p_0603"))
    )
    (comp (ref "R62")
      (value "10k 5%")
      (footprint "RES_0603")
      (description "Resistor 0603 5% 0,1W")
      (fields (field (name "TOLERANCE") "5%") (field (name "VOLTAGE") "50"))
      (libsource (lib "WB") (part "RES_10k_5p_0603"))
    )
    (comp (ref "R63")
      (value "10k 5%")
      (footprint "RES_0603")
      (description "Resistor 0603 5% 0,1W")
      (fields (field (name "TOLERANCE") "5%") (field (name "VOLTAGE") "50"))
      (libsource (lib "") (part "RES_10k_5p_0603_1"))
    )
    (comp (ref "R64")
      (value "220k")
      (footprint "RES_0603")
      (description "Resistor 0603 5% 0,1W")
      (fields (field (name "TOLERANCE") "5%") (field (name "VOLTAGE") "50"))
      (libsource (lib "WB") (part "RES_100k_5p_0603"))
    )
    (comp (ref "R65")
      (value "1k 5%")
      (footprint "RES_0603")
      (description "Resistor 0603 5% 0,1W")
      (fields (field (name "MANUFACTURER") "YAGEO") (field (name "TOLERANCE") "5%"))
      (libsource (lib "WB") (part "RES_1k_5p_0603"))
    )
    (comp (ref "R66")
      (value "4M7 5%")
      (footprint "RES_1206")
      (description "Resistor 1206 5% 0,25W")
      (fields
        (field (name "MANUFACTURER") "ROYAL OHM")
        (field (name "MANUFACTURER PART NUMBER") "1206S4J0475T5E")
      )
      (libsource (lib "") (part "RES_4M7_5p_1206_2"))
    )
    (comp (ref "R67")
      (value "10k 5%")
      (footprint "RES_0603")
      (description "Resistor 0603 5% 0,1W")
      (fields (field (name "TOLERANCE") "5%") (field (name "VOLTAGE") "50"))
      (libsource (lib "WB") (part "RES_10k_5p_0603"))
    )
    (comp (ref "R68")
      (value "DNP")
      (footprint "RES_0603")
      (description "Resistor 0603 5% 0,1W")
      (fields (field (name "MANUFACTURER") "YAGEO") (field (name "TOLERANCE") "5%"))
      (libsource (lib "") (part "RES_16k_5p_0603_3"))
    )
    (comp (ref "R69")
      (value "47k 5%")
      (footprint "RES_0603")
      (description "Resistor 0603 5% 0,1W")
      (fields (field (name "MANUFACTURER") "YAGEO") (field (name "TOLERANCE") "5%"))
      (libsource (lib "WB") (part "RES_47k_5p_0603"))
    )
    (comp (ref "R70")
      (value "100k 5%")
      (footprint "RES_0603")
      (description "Resistor 0603 5% 0,1W")
      (fields (field (name "TOLERANCE") "5%") (field (name "VOLTAGE") "50"))
      (libsource (lib "") (part "RES_100k_5p_0603_1"))
    )
    (comp (ref "R71")
      (value "330 5%")
      (footprint "RES_0603")
      (description "Resistor 0603 5% 0,1W")
      (fields (field (name "TOLERANCE") "5%") (field (name "VOLTAGE") "50"))
      (libsource (lib "WB") (part "RES_330R_5p_0603"))
    )
    (comp (ref "R72")
      (value "4M7 5%")
      (footprint "RES_1206")
      (description "Resistor 1206 5% 0,25W")
      (fields
        (field (name "MANUFACTURER") "ROYAL OHM")
        (field (name "MANUFACTURER PART NUMBER") "1206S4J0475T5E")
      )
      (libsource (lib "") (part "RES_4M7_5p_1206_1"))
    )
    (comp (ref "RT1")
      (value "NTCS0603E3683FHT")
      (footprint "RES_0603")
      (description "Thermistor 0603 ,063W Stała materiałowa B     3985K")
      (fields (field (name "MANUFACTURER") "VISHAY"))
      (libsource (lib "WB") (part "REST_10k_0603"))
    )
    (comp (ref "RT2")
      (value "NTCS0603E3683FHT")
      (footprint "RES_0603")
      (description "Thermistor 0603 ,063W Stała materiałowa B     3985K")
      (fields (field (name "MANUFACTURER") "VISHAY"))
      (libsource (lib "WB") (part "REST_10k_0603"))
    )
    (comp (ref "RT3")
      (value "NTCS0603E3683FHT")
      (footprint "RES_0603")
      (description "Thermistor 0603 ,063W Stała materiałowa B     3985K")
      (fields (field (name "MANUFACTURER") "VISHAY"))
      (libsource (lib "WB") (part "REST_10k_0603"))
    )
    (comp (ref "RV1")
      (value "50VAC 1kA")
      (footprint "RES_VAR_S14")
      (description "warystor S14 30VAC 38VDC 1kA 9J@2ms")
      (fields (field (name "MANUFACTURER") "EPCOS") (field (name "TOLERANCE") "10%"))
      (libsource (lib "WB") (part "RESV_38V_1kA_THT"))
    )
    (comp (ref "T1")
      (value "IPD034N06N3GATMA1")
      (footprint "DPAK_369C_issueD")
      (description "60V N-Mosfet 100A 60V 3.54mohm")
      (fields (field (name "MANUFACTURER") "INFINEON"))
      (libsource (lib "WB") (part "T_IPD034N06N3"))
    )
    (comp (ref "T2")
      (value "IPD034N06N3GATMA1")
      (footprint "DPAK_369C_issueD")
      (description "60V N-Mosfet 100A 60V 3.54mohm")
      (fields (field (name "MANUFACTURER") "INFINEON"))
      (libsource (lib "WB") (part "T_IPD034N06N3"))
    )
    (comp (ref "T3")
      (value "IPD034N06N3GATMA1")
      (footprint "DPAK_369C_issueD")
      (description "60V N-Mosfet 100A 60V 3.54mohm")
      (fields (field (name "MANUFACTURER") "INFINEON"))
      (libsource (lib "WB") (part "T_IPD034N06N3"))
    )
    (comp (ref "T4")
      (value "IPD034N06N3GATMA1")
      (footprint "DPAK_369C_issueD")
      (description "60V N-Mosfet 100A 60V 3.54mohm")
      (fields (field (name "MANUFACTURER") "INFINEON"))
      (libsource (lib "WB") (part "T_IPD034N06N3"))
    )
    (comp (ref "T5")
      (value "2N7002-7-F")
      (footprint "SOT23-3")
      (description "60V 0.21A N mosfet")
      (fields (field (name "MANUFACTURER") "DIODES") (field (name "VOLTAGE") "60V"))
      (libsource (lib "WB") (part "T_2N7002"))
    )
    (comp (ref "T6")
      (value "IPD034N06N3GATMA1")
      (footprint "DPAK_369C_issueD")
      (description "60V N-Mosfet 100A 60V 3.54mohm")
      (fields (field (name "MANUFACTURER") "INFINEON"))
      (libsource (lib "WB") (part "T_IPD034N06N3"))
    )
    (comp (ref "T7")
      (value "IPD034N06N3GATMA1")
      (footprint "DPAK_369C_issueD")
      (description "60V N-Mosfet 100A 60V 3.54mohm")
      (fields (field (name "MANUFACTURER") "INFINEON"))
      (libsource (lib "WB") (part "T_IPD034N06N3"))
    )
    (comp (ref "T8")
      (value "2N7002-7-F")
      (footprint "SOT23-3")
      (description "60V 0.21A N mosfet")
      (fields (field (name "MANUFACTURER") "DIODES") (field (name "VOLTAGE") "60V"))
      (libsource (lib "WB") (part "T_2N7002"))
    )
    (comp (ref "T9")
      (value "2N7002-7-F")
      (footprint "SOT23-3")
      (description "60V 0.21A N mosfet")
      (fields (field (name "MANUFACTURER") "DIODES") (field (name "VOLTAGE") "60V"))
      (libsource (lib "WB") (part "T_2N7002"))
    )
    (comp (ref "T10")
      (value "2N7002-7-F")
      (footprint "SOT23-3")
      (description "60V 0.21A N mosfet")
      (fields (field (name "MANUFACTURER") "DIODES") (field (name "VOLTAGE") "60V"))
      (libsource (lib "WB") (part "T_2N7002"))
    )
    (comp (ref "T11")
      (value "HCPL817-300E")
      (footprint "HCPL-817")
      (description "HCPL817-300E\r\n'0' ctr 50-600%\r\nif 20ma ic 30ma vce 70V vr 4v")
      (fields (field (name "MANUFACTURER PART NUMBER") "HCPL-817-36BE"))
      (libsource (lib "WB") (part "T_HCPL817-300E"))
    )
    (comp (ref "T12")
      (value "IPD034N06N3GATMA1")
      (footprint "DPAK_369C_issueD")
      (description "60V N-Mosfet 100A 60V 3.54mohm")
      (fields (field (name "MANUFACTURER") "INFINEON"))
      (libsource (lib "WB") (part "T_IPD034N06N3"))
    )
    (comp (ref "T13")
      (value "IPD034N06N3GATMA1")
      (footprint "DPAK_369C_issueD")
      (description "60V N-Mosfet 100A 60V 3.54mohm")
      (fields (field (name "MANUFACTURER") "INFINEON"))
      (libsource (lib "WB") (part "T_IPD034N06N3"))
    )
    (comp (ref "T14")
      (value "IPD034N06N3GATMA1")
      (footprint "DPAK_369C_issueD")
      (description "60V N-Mosfet 100A 60V 3.54mohm")
      (fields (field (name "MANUFACTURER") "INFINEON"))
      (libsource (lib "WB") (part "T_IPD034N06N3"))
    )
    (comp (ref "T15")
      (value "2N7002-7-F")
      (footprint "SOT23-3")
      (description "60V 0.21A N mosfet")
      (fields (field (name "MANUFACTURER") "DIODES") (field (name "VOLTAGE") "60V"))
      (libsource (lib "WB") (part "T_2N7002"))
    )
    (comp (ref "T16")
      (value "2N7002-7-F")
      (footprint "SOT23-3")
      (description "60V 0.21A N mosfet")
      (fields (field (name "MANUFACTURER") "DIODES") (field (name "VOLTAGE") "60V"))
      (libsource (lib "WB") (part "T_2N7002"))
    )
    (comp (ref "U1")
      (value "TPS57160QDGQRQ1")
      (footprint "MSOP10_DQG_S_PDSO_G10")
      (description "116uA quescient current")
      (fields (field (name "MANUFACTURER") "Texas Instruments"))
      (libsource (lib "WB") (part "IC_TPS57160QDGQRQ1"))
    )
    (comp (ref "U2")
      (value "LMV772QMM/NOPB")
      (footprint "MSOP8_3x3_846AD-01")
      (description "LowOffset,LowNoise,RROOperationalAmplifier")
      (fields (field (name "MANUFACTURER") "TI National Semiconductor"))
      (libsource (lib "WB") (part "IC_LMV772QMM"))
    )
    (comp (ref "U3")
      (value "WT8266-S2")
      (footprint "MOD_WT8266-S2")
      (fields (field (name "MANUFACTURER") "xiaoe") (field (name "VOLTAGE") "3.0 - 3.6"))
      (libsource (lib "WB") (part "MOD_WT8266-S2"))
    )
    (comp (ref "U4")
      (value "MCP1703A-3302")
      (footprint "sot223")
      (description "LDO=210mV 6V DC max, Iq 120uA, Cout 1u ceramic")
      (fields (field (name "MANUFACTURER") "Microchip") (field (name "VOLTAGE") "6V"))
      (libsource (lib "WB") (part "IC_MCP1825S-3.3_SOT223"))
    )
    (comp (ref "U5")
      (value "IC_STM32L431RCT6_LQFP64")
      (footprint "LQFP64_10x10")
      (description "LQFP64, 10x10mm")
      (fields
        (field (name "MANUFACTURER") "STMicroelectronics")
        (field (name "MANUFACTURER PART NUMBER") "STM32L431RCT6")
      )
      (libsource (lib "WB") (part "IC_STM32L431RCT6_LQFP64"))
    )
    (comp (ref "X1")
      (value "OSCX_8M_5,0x3,2")
      (footprint "X_5.0X3.2")
      (description "SMD 5,0x3,2mm xtal drive 100uW max; ESR 150 ohm")
      (fields
        (field (name "MANUFACTURER") "Abracon")
        (field (name "MANUFACTURER PART NUMBER") "ABM3-8.000MHZ-D2Y-T")
      )
      (libsource (lib "WB") (part "OSCX_8M_5,0x3,2"))
    )
  )
  (nets
    (net (code "1") (name "+3") (class "Default")
      (node (ref "C24") (pin "1") (pinfunction "1_1") (pintype "passive"))
      (node (ref "C25") (pin "1") (pinfunction "1_1") (pintype "passive"))
      (node (ref "C30") (pin "1") (pinfunction "1_1") (pintype "passive"))
      (node (ref "C39") (pin "1") (pinfunction "1_1") (pintype "passive"))
      (node (ref "C40") (pin "1") (pinfunction "1_1") (pintype "passive"))
      (node (ref "C41") (pin "1") (pinfunction "1_1") (pintype "passive"))
      (node (ref "C42") (pin "1") (pinfunction "1_1") (pintype "passive"))
      (node (ref "J5") (pin "4") (pinfunction "VDD_4") (pintype "power_in"))
      (node (ref "Q2") (pin "2") (pinfunction "S_2") (pintype "passive"))
      (node (ref "R43") (pin "1") (pinfunction "1_1") (pintype "passive"))
      (node (ref "R44") (pin "1") (pinfunction "1_1") (pintype "passive"))
      (node (ref "R45") (pin "1") (pinfunction "1_1") (pintype "passive"))
      (node (ref "R46") (pin "1") (pinfunction "1_1") (pintype "passive"))
      (node (ref "R48") (pin "1") (pinfunction "1_1") (pintype "passive"))
      (node (ref "R50") (pin "1") (pinfunction "1_1") (pintype "passive"))
      (node (ref "R53") (pin "2") (pinfunction "2_2") (pintype "passive"))
      (node (ref "R67") (pin "1") (pinfunction "1_1") (pintype "passive"))
      (node (ref "U4") (pin "3") (pinfunction "OUT_3") (pintype "power_in"))
      (node (ref "U5") (pin "1") (pinfunction "VBAT/VLCD_1") (pintype "passive"))
      (node (ref "U5") (pin "13") (pinfunction "VDDA/VREF+_13") (pintype "passive"))
      (node (ref "U5") (pin "19") (pinfunction "VDD/PF5_19") (pintype "passive"))
      (node (ref "U5") (pin "32") (pinfunction "VDD_32") (pintype "passive"))
      (node (ref "U5") (pin "48") (pinfunction "VDD/VUSB/VSA/PF7_48") (pintype "passive"))
      (node (ref "U5") (pin "64") (pinfunction "VDD_64") (pintype "passive"))
    )
    (net (code "2") (name "+3_ESP") (class "Default")
      (node (ref "C31") (pin "1") (pinfunction "1_1") (pintype "passive"))
      (node (ref "L3") (pin "1") (pinfunction "1_1") (pintype "passive"))
      (node (ref "Q2") (pin "3") (pinfunction "D_3") (pintype "passive"))
      (node (ref "R24") (pin "2") (pinfunction "2_2") (pintype "passive"))
      (node (ref "R27") (pin "1") (pinfunction "1_1") (pintype "passive"))
      (node (ref "R29") (pin "1") (pinfunction "1_1") (pintype "passive"))
      (node (ref "R30") (pin "1") (pinfunction "1_1") (pintype "passive"))
      (node (ref "R31") (pin "1") (pinfunction "1_1") (pintype "passive"))
      (node (ref "R32") (pin "1") (pinfunction "1_1") (pintype "passive"))
      (node (ref "R55") (pin "1") (pinfunction "1_1") (pintype "passive"))
      (node (ref "U3") (pin "1") (pinfunction "VCC_1") (pintype "power_in"))
    )
    (net (code "3") (name "+5") (class "Default")
      (node (ref "C26") (pin "1") (pinfunction "1_1") (pintype "passive"))
      (node (ref "C27") (pin "1") (pinfunction "1_1") (pintype "passive"))
      (node (ref "C4") (pin "2") (pinfunction "2_2") (pintype "passive"))
      (node (ref "C5") (pin "2") (pinfunction "2_2") (pintype "passive"))
      (node (ref "C8") (pin "1") (pinfunction "1_1") (pintype "passive"))
      (node (ref "C9") (pin "1") (pinfunction "1_1") (pintype "passive"))
      (node (ref "D3") (pin "1") (pinfunction "A_1") (pintype "passive"))
      (node (ref "D5") (pin "1") (pinfunction "A_1") (pintype "passive"))
      (node (ref "D6") (pin "2") (pinfunction "K_2") (pintype "passive"))
      (node (ref "L1") (pin "2") (pinfunction "2_2") (pintype "passive"))
      (node (ref "L2") (pin "1") (pinfunction "1_1") (pintype "passive"))
      (node (ref "Q1") (pin "2") (pinfunction "S_2") (pintype "passive"))
      (node (ref "R35") (pin "1") (pinfunction "1_1") (pintype "passive"))
      (node (ref "R5") (pin "2") (pinfunction "2_2") (pintype "passive"))
      (node (ref "R63") (pin "1") (pinfunction "1_1") (pintype "passive"))
      (node (ref "U4") (pin "1") (pinfunction "VI_1") (pintype "input"))
    )
    (net (code "4") (name "/BATT_BCKP_DRV") (class "Default")
      (node (ref "T16") (pin "1") (pinfunction "G_1") (pintype "passive"))
      (node (ref "U5") (pin "20") (pinfunction "PA4/SPI1_NSS/ADC1_IN9/LPTIM2_OUT/DAC1_OUT_20") (pintype "passive"))
    )
    (net (code "5") (name "/BAT_SWITCH_OFF") (class "Default")
      (node (ref "T8") (pin "1") (pinfunction "G_1") (pintype "passive"))
      (node (ref "U5") (pin "22") (pinfunction "PA6/SPI1_MISO/TIM1_BKIN/TIM16_CH1/ADC1_IN11_22") (pintype "passive"))
    )
    (net (code "6") (name "/BAT_SWITCH_PWM") (class "Default")
      (node (ref "R39") (pin "2") (pinfunction "2_2") (pintype "passive"))
      (node (ref "T10") (pin "1") (pinfunction "G_1") (pintype "passive"))
      (node (ref "T9") (pin "1") (pinfunction "G_1") (pintype "passive"))
      (node (ref "U5") (pin "21") (pinfunction "PA5/TIM2_CH1/SPI1_SCK/ADC1_IN10/DAC1_OUT2_21") (pintype "passive"))
    )
    (net (code "7") (name "/BAT_VOLTAGE") (class "Default")
      (node (ref "C35") (pin "1") (pinfunction "1_1") (pintype "passive"))
      (node (ref "R37") (pin "1") (pinfunction "1_1") (pintype "passive"))
      (node (ref "R40") (pin "2") (pinfunction "2_2") (pintype "passive"))
      (node (ref "U5") (pin "11") (pinfunction "PC3/ADC1IN4/SPI2_MOSI/LPTIM1_ETR/SAI1_SD_A/LPTIM2_ETR_11") (pintype "passive"))
    )
    (net (code "8") (name "/C1") (class "Default")
      (node (ref "K1") (pin "1") (pinfunction "1_1") (pintype "passive"))
      (node (ref "R43") (pin "2") (pinfunction "2_2") (pintype "passive"))
      (node (ref "U5") (pin "25") (pinfunction "PC5/USART3_RX/COMP1_INP/ADC1_IN14/WKUP5_25") (pintype "passive"))
    )
    (net (code "9") (name "/C2") (class "Default")
      (node (ref "K1") (pin "2") (pinfunction "2_2") (pintype "passive"))
      (node (ref "R44") (pin "2") (pinfunction "2_2") (pintype "passive"))
      (node (ref "U5") (pin "27") (pinfunction "COMP1_INM/ADC1_IN16/LPTIM2_IN1/TIM1_CH3N/PB1/VREF+_27") (pintype "passive"))
    )
    (net (code "10") (name "/C3") (class "Default")
      (node (ref "K1") (pin "4") (pinfunction "4_4") (pintype "passive"))
      (node (ref "R45") (pin "2") (pinfunction "2_2") (pintype "passive"))
      (node (ref "U5") (pin "24") (pinfunction "PC4/USART3_TX/COMP1_INM/ADC1_IN13_24") (pintype "passive"))
    )
    (net (code "11") (name "/C4") (class "Default")
      (node (ref "K1") (pin "8") (pinfunction "8_8") (pintype "passive"))
      (node (ref "R46") (pin "2") (pinfunction "2_2") (pintype "passive"))
      (node (ref "U5") (pin "26") (pinfunction "ADC1_IN15/COMP1_OUT/TIM1_CH2N/SPI1_NSS/PB0_26") (pintype "passive"))
    )
    (net (code "12") (name "/ESP_RX") (class "Default")
      (node (ref "U3") (pin "11") (pinfunction "U0TXD/IO1_11") (pintype "bidirectional"))
      (node (ref "U5") (pin "30") (pinfunction "COMP2_OUT/LPUART1_TX/USART3_RX/I2C2_SDA/TIM2_CH4/PB11/VCAP1_30") (pintype "passive"))
    )
    (net (code "13") (name "/ESP_TX") (class "Default")
      (node (ref "U3") (pin "9") (pinfunction "U0RXD/IO3_9") (pintype "bidirectional"))
      (node (ref "U5") (pin "29") (pinfunction "LPUART1_RX/USART3_TX/SPI2_SCK/I2C2_SCL/TIM2_CH3/PB10_29") (pintype "passive"))
    )
    (net (code "14") (name "/EXT_I") (class "Default")
      (node (ref "C46") (pin "2") (pinfunction "2_2") (pintype "passive"))
      (node (ref "D16") (pin "2") (pinfunction "K_2") (pintype "passive"))
      (node (ref "R64") (pin "1") (pinfunction "1_1") (pintype "passive"))
      (node (ref "U5") (pin "62") (pinfunction "SDMMC1_D5/CAN1_TX/SPI2_NSS/I2C1_SDA/IR_OUT/PB9_62") (pintype "passive"))
    )
    (net (code "15") (name "/EXT_IN") (class "Default")
      (node (ref "R58") (pin "1") (pinfunction "1_1") (pintype "passive"))
      (node (ref "R60") (pin "1") (pinfunction "1_1") (pintype "passive"))
      (node (ref "T11") (pin "3") (pinfunction "E_3") (pintype "passive"))
      (node (ref "U5") (pin "17") (pinfunction "PA3/SAR_VREF+/TIM2_CH4/ADC1IN8/COMP2_INP_17") (pintype "passive"))
    )
    (net (code "16") (name "/EXT_O") (class "Default")
      (node (ref "T15") (pin "1") (pinfunction "G_1") (pintype "passive"))
      (node (ref "U5") (pin "61") (pinfunction "TIM16_CH1/SDMMC1_D4/CAN1_RX/I2C1_SCL/PB8_61") (pintype "passive"))
    )
    (net (code "17") (name "/INV_CURRENT") (class "Default")
      (node (ref "C22") (pin "1") (pinfunction "1_1") (pintype "passive"))
      (node (ref "R19") (pin "2") (pinfunction "2_2") (pintype "passive"))
      (node (ref "U5") (pin "8") (pinfunction "PC0/ADC1IN1/LPUART1RX/LPTIM1_IN1/I2C3_SCL/LPTIM2_IN1_8") (pintype "passive"))
    )
    (net (code "18") (name "/INV_SWITCH") (class "Default")
      (node (ref "R16") (pin "2") (pinfunction "2_2") (pintype "passive"))
      (node (ref "R17") (pin "1") (pinfunction "1_1") (pintype "passive"))
      (node (ref "R28") (pin "1") (pinfunction "1_1") (pintype "passive"))
      (node (ref "T1") (pin "1") (pinfunction "G_1") (pintype "passive"))
      (node (ref "T12") (pin "1") (pinfunction "G_1") (pintype "passive"))
      (node (ref "T2") (pin "1") (pinfunction "G_1") (pintype "passive"))
    )
    (net (code "19") (name "/INV_SWITCH_DRV") (class "Default")
      (node (ref "R62") (pin "2") (pinfunction "2_2") (pintype "passive"))
      (node (ref "T5") (pin "1") (pinfunction "G_1") (pintype "passive"))
      (node (ref "U5") (pin "23") (pinfunction "PA7/TIM1_CH1N/I2C3_SCL/SPI1_MOSI/COMP2_OUT/ADC1_IN12_23") (pintype "passive"))
    )
    (net (code "20") (name "/LED_1") (class "Default")
      (node (ref "R47") (pin "2") (pinfunction "2_2") (pintype "passive"))
      (node (ref "U5") (pin "36") (pinfunction "TIM15_CH2/SPI2_MOSI/TIM1_CH3N/RTC_REFIN/PB15_36") (pintype "passive"))
    )
    (net (code "21") (name "/LED_2") (class "Default")
      (node (ref "R49") (pin "2") (pinfunction "2_2") (pintype "passive"))
      (node (ref "U5") (pin "35") (pinfunction "TIM15_CH1/SWPMI1_RX/SPI2_MISO/I2C2_SDA/TIM1_CH2N/PB14_35") (pintype "passive"))
    )
    (net (code "22") (name "/LED_3") (class "Default")
      (node (ref "R52") (pin "2") (pinfunction "2_2") (pintype "passive"))
      (node (ref "U5") (pin "34") (pinfunction "SWPMI1_TX/TIM15_CH1N/SPI2_SCK/I2C2_SCL/TIM1_CH1N/PB13_34") (pintype "passive"))
    )
    (net (code "23") (name "/LED_4") (class "Default")
      (node (ref "R54") (pin "2") (pinfunction "2_2") (pintype "passive"))
      (node (ref "U5") (pin "33") (pinfunction "TIM15_BKIN/SPI2_NSS/I2C2_SMBA/TIM1_BKIN/PB12/SD_VREF+_33") (pintype "passive"))
    )
    (net (code "24") (name "/MEAS_PWR") (class "Default")
      (node (ref "Q2") (pin "1") (pinfunction "G_1") (pintype "passive"))
      (node (ref "U5") (pin "41") (pinfunction "PA8/TIM1_CH1/SAI1_SCK_A/LPTIM2_OUT/USART1_CK_41") (pintype "passive"))
    )
    (net (code "25") (name "/NRST") (class "Default")
      (node (ref "C38") (pin "1") (pinfunction "1_1") (pintype "passive"))
      (node (ref "J6") (pin "5") (pinfunction "5_5") (pintype "passive"))
      (node (ref "R48") (pin "2") (pinfunction "2_2") (pintype "passive"))
      (node (ref "U5") (pin "7") (pinfunction "NRST_7") (pintype "passive"))
    )
    (net (code "26") (name "/NTC1") (class "Default")
      (node (ref "R32") (pin "2") (pinfunction "2_2") (pintype "passive"))
      (node (ref "RT3") (pin "1") (pinfunction "1_1") (pintype "passive"))
      (node (ref "U5") (pin "14") (pinfunction "PA0/ADC1IN5/TIM2_CH1/COMP1_OUT/OPAMP1_VINP/WKUP1_14") (pintype "passive"))
    )
    (net (code "27") (name "/NTC2") (class "Default")
      (node (ref "R30") (pin "2") (pinfunction "2_2") (pintype "passive"))
      (node (ref "RT1") (pin "1") (pinfunction "1_1") (pintype "passive"))
      (node (ref "U5") (pin "15") (pinfunction "PA1/ADC1IN6/TIM2_CH2/SPI1_SCK/I2C1_SMBA/SPI1_SCK_15") (pintype "passive"))
    )
    (net (code "28") (name "/NTC3") (class "Default")
      (node (ref "R31") (pin "2") (pinfunction "2_2") (pintype "passive"))
      (node (ref "RT2") (pin "1") (pinfunction "1_1") (pintype "passive"))
      (node (ref "U5") (pin "16") (pinfunction "PA2/ADC1IN7/TIM2_CH3/U2_TX/WKUP4/TIM15_CH1/LPUART1_TX_16") (pintype "passive"))
    )
    (net (code "29") (name "/PV_CURRENT") (class "Default")
      (node (ref "C23") (pin "1") (pinfunction "1_1") (pintype "passive"))
      (node (ref "R20") (pin "2") (pinfunction "2_2") (pintype "passive"))
      (node (ref "U5") (pin "9") (pinfunction "PC1/ADC1IN2/LPUART1TX/LPTIM1_OUT/I2C3_SDA_9") (pintype "passive"))
    )
    (net (code "30") (name "/PV_VOLTAGE") (class "Default")
      (node (ref "C12") (pin "1") (pinfunction "1_1") (pintype "passive"))
      (node (ref "R14") (pin "2") (pinfunction "2_2") (pintype "passive"))
      (node (ref "R6") (pin "1") (pinfunction "1_1") (pintype "passive"))
      (node (ref "U5") (pin "10") (pinfunction "PC2/ADC1IN3/SPI2_MISO/LPTIM1_IN2_10") (pintype "passive"))
    )
    (net (code "31") (name "/SD_CMD") (class "Default")
      (node (ref "J5") (pin "3") (pinfunction "CMD_3") (pintype "input"))
      (node (ref "U5") (pin "54") (pinfunction "SDMMC1_CMD/TSC_SYNC/PD2_54") (pintype "passive"))
    )
    (net (code "32") (name "/SD_DET") (class "Default")
      (node (ref "R68") (pin "1") (pinfunction "1_1") (pintype "passive"))
      (node (ref "U5") (pin "28") (pinfunction "COMP1_INP/I2C3_SMBA/LPTIM1_OUT/RTC_OUT/PB2_28") (pintype "passive"))
    )
    (net (code "33") (name "/SWDCLK") (class "Default")
      (node (ref "J6") (pin "2") (pinfunction "2_2") (pintype "passive"))
      (node (ref "U5") (pin "49") (pinfunction "PA14/JTCK-SWCLK/LPTIM1_OUT/I2C1_SMBA_49") (pintype "passive"))
    )
    (net (code "34") (name "/SWDIO") (class "Default")
      (node (ref "J6") (pin "4") (pinfunction "4_4") (pintype "passive"))
      (node (ref "U5") (pin "46") (pinfunction "PA13/JTMS-SWDIO/IR_OUT/SWPMI1_TX_46") (pintype "passive"))
    )
    (net (code "35") (name "/TRACE_SWO") (class "Default")
      (node (ref "J6") (pin "6") (pinfunction "6_6") (pintype "passive"))
      (node (ref "U5") (pin "55") (pinfunction "SPI1_SCK/TIM2_CH2/JTDO-TRACESWO/PB3_55") (pintype "passive"))
    )
    (net (code "36") (name "/V_GATE") (class "Default")
      (node (ref "C33") (pin "1") (pinfunction "1_1") (pintype "passive"))
      (node (ref "D7") (pin "2") (pinfunction "K_2") (pintype "passive"))
      (node (ref "R33") (pin "1") (pinfunction "1_1") (pintype "passive"))
      (node (ref "R34") (pin "2") (pinfunction "2_2") (pintype "passive"))
      (node (ref "T13") (pin "1") (pinfunction "G_1") (pintype "passive"))
      (node (ref "T14") (pin "1") (pinfunction "G_1") (pintype "passive"))
      (node (ref "T3") (pin "1") (pinfunction "G_1") (pintype "passive"))
      (node (ref "T4") (pin "1") (pinfunction "G_1") (pintype "passive"))
      (node (ref "T6") (pin "1") (pinfunction "G_1") (pintype "passive"))
      (node (ref "T7") (pin "1") (pinfunction "G_1") (pintype "passive"))
    )
    (net (code "37") (name "/V_SOURCE") (class "Default")
      (node (ref "C28") (pin "2") (pinfunction "2_2") (pintype "passive"))
      (node (ref "C29") (pin "1") (pinfunction "1_1") (pintype "passive"))
      (node (ref "C33") (pin "2") (pinfunction "2_2") (pintype "passive"))
      (node (ref "R25") (pin "2") (pinfunction "2_2") (pintype "passive"))
      (node (ref "R26") (pin "1") (pinfunction "1_1") (pintype "passive"))
      (node (ref "R34") (pin "1") (pinfunction "1_1") (pintype "passive"))
      (node (ref "R36") (pin "1") (pinfunction "1_1") (pintype "passive"))
      (node (ref "T13") (pin "3") (pinfunction "S_3") (pintype "passive"))
      (node (ref "T14") (pin "3") (pinfunction "S_3") (pintype "passive"))
      (node (ref "T3") (pin "3") (pinfunction "S_3") (pintype "passive"))
      (node (ref "T4") (pin "3") (pinfunction "S_3") (pintype "passive"))
      (node (ref "T6") (pin "3") (pinfunction "S_3") (pintype "passive"))
      (node (ref "T7") (pin "3") (pinfunction "S_3") (pintype "passive"))
    )
    (net (code "38") (name "/rx") (class "Default")
      (node (ref "J4") (pin "2") (pinfunction "2_2") (pintype "passive"))
      (node (ref "R42") (pin "1") (pinfunction "1_1") (pintype "passive"))
      (node (ref "R67") (pin "2") (pinfunction "2_2") (pintype "passive"))
    )
    (net (code "39") (name "/tx") (class "Default")
      (node (ref "J4") (pin "1") (pinfunction "1_1") (pintype "passive"))
      (node (ref "R41") (pin "1") (pinfunction "1_1") (pintype "passive"))
    )
    (net (code "40") (name "GND") (class "Default")
      (node (ref "C10") (pin "2") (pinfunction "2_2") (pintype "passive"))
      (node (ref "C11") (pin "1") (pinfunction "1_1") (pintype "passive"))
      (node (ref "C12") (pin "2") (pinfunction "2_2") (pintype "passive"))
      (node (ref "C13") (pin "2") (pinfunction "2_2") (pintype "passive"))
      (node (ref "C14") (pin "2") (pinfunction "2_2") (pintype "passive"))
      (node (ref "C17") (pin "2") (pinfunction "2_2") (pintype "passive"))
      (node (ref "C18") (pin "2") (pinfunction "2_2") (pintype "passive"))
      (node (ref "C19") (pin "2") (pinfunction "2_2") (pintype "passive"))
      (node (ref "C2") (pin "1") (pinfunction "1_1") (pintype "passive"))
      (node (ref "C20") (pin "2") (pinfunction "2_2") (pintype "passive"))
      (node (ref "C21") (pin "2") (pinfunction "2_2") (pintype "passive"))
      (node (ref "C22") (pin "2") (pinfunction "2_2") (pintype "passive"))
      (node (ref "C23") (pin "2") (pinfunction "2_2") (pintype "passive"))
      (node (ref "C24") (pin "2") (pinfunction "2_2") (pintype "passive"))
      (node (ref "C25") (pin "2") (pinfunction "2_2") (pintype "passive"))
      (node (ref "C26") (pin "2") (pinfunction "2_2") (pintype "passive"))
      (node (ref "C27") (pin "2") (pinfunction "2_2") (pintype "passive"))
      (node (ref "C3") (pin "1") (pinfunction "1_1") (pintype "passive"))
      (node (ref "C30") (pin "2") (pinfunction "2_2") (pintype "passive"))
      (node (ref "C31") (pin "2") (pinfunction "2_2") (pintype "passive"))
      (node (ref "C32") (pin "2") (pinfunction "2_2") (pintype "passive"))
      (node (ref "C35") (pin "2") (pinfunction "2_2") (pintype "passive"))
      (node (ref "C36") (pin "1") (pinfunction "1_1") (pintype "passive"))
      (node (ref "C37") (pin "1") (pinfunction "1_1") (pintype "passive"))
      (node (ref "C38") (pin "2") (pinfunction "2_2") (pintype "passive"))
      (node (ref "C39") (pin "2") (pinfunction "2_2") (pintype "passive"))
      (node (ref "C4") (pin "1") (pinfunction "1_1") (pintype "passive"))
      (node (ref "C40") (pin "2") (pinfunction "2_2") (pintype "passive"))
      (node (ref "C41") (pin "2") (pinfunction "2_2") (pintype "passive"))
      (node (ref "C42") (pin "2") (pinfunction "2_2") (pintype "passive"))
      (node (ref "C43") (pin "1") (pinfunction "1_1") (pintype "passive"))
      (node (ref "C46") (pin "1") (pinfunction "1_1") (pintype "passive"))
      (node (ref "C47") (pin "2") (pinfunction "2_2") (pintype "passive"))
      (node (ref "C48") (pin "1") (pinfunction "1_1") (pintype "passive"))
      (node (ref "C5") (pin "1") (pinfunction "1_1") (pintype "passive"))
      (node (ref "C7") (pin "2") (pinfunction "2_2") (pintype "passive"))
      (node (ref "C8") (pin "2") (pinfunction "2_2") (pintype "passive"))
      (node (ref "C9") (pin "2") (pinfunction "2_2") (pintype "passive"))
      (node (ref "D10") (pin "2") (pinfunction "K_2") (pintype "passive"))
      (node (ref "D11") (pin "2") (pinfunction "K_2") (pintype "passive"))
      (node (ref "D12") (pin "2") (pinfunction "K_2") (pintype "passive"))
      (node (ref "D13") (pin "2") (pinfunction "K_2") (pintype "passive"))
      (node (ref "D15") (pin "1") (pinfunction "A_1") (pintype "passive"))
      (node (ref "D17") (pin "1") (pinfunction "A_1") (pintype "passive"))
      (node (ref "D4") (pin "1") (pinfunction "A_1") (pintype "passive"))
      (node (ref "J2") (pin "2") (pinfunction "2_2") (pintype "passive"))
      (node (ref "J4") (pin "3") (pinfunction "3_3") (pintype "passive"))
      (node (ref "J5") (pin "6") (pinfunction "GND_6") (pintype "power_in"))
      (node (ref "J6") (pin "3") (pinfunction "3_3") (pintype "passive"))
      (node (ref "K1") (pin "C") (pinfunction "C_C") (pintype "passive"))
      (node (ref "R11") (pin "2") (pinfunction "2_2") (pintype "passive"))
      (node (ref "R12") (pin "1") (pinfunction "1_1") (pintype "passive"))
      (node (ref "R13") (pin "1") (pinfunction "1_1") (pintype "passive"))
      (node (ref "R14") (pin "1") (pinfunction "1_1") (pintype "passive"))
      (node (ref "R15") (pin "1") (pinfunction "1_1") (pintype "passive"))
      (node (ref "R21") (pin "1") (pinfunction "1_1") (pintype "passive"))
      (node (ref "R3") (pin "2") (pinfunction "2_2") (pintype "passive"))
      (node (ref "R39") (pin "1") (pinfunction "1_1") (pintype "passive"))
      (node (ref "R40") (pin "1") (pinfunction "1_1") (pintype "passive"))
      (node (ref "R51") (pin "1") (pinfunction "1_1") (pintype "passive"))
      (node (ref "R58") (pin "2") (pinfunction "2_2") (pintype "passive"))
      (node (ref "R62") (pin "1") (pinfunction "1_1") (pintype "passive"))
      (node (ref "R64") (pin "2") (pinfunction "2_2") (pintype "passive"))
      (node (ref "R66") (pin "1") (pinfunction "1_1") (pintype "passive"))
      (node (ref "R68") (pin "2") (pinfunction "2_2") (pintype "passive"))
      (node (ref "R7") (pin "1") (pinfunction "1_1") (pintype "passive"))
      (node (ref "RT1") (pin "2") (pinfunction "2_2") (pintype "passive"))
      (node (ref "RT2") (pin "2") (pinfunction "2_2") (pintype "passive"))
      (node (ref "RT3") (pin "2") (pinfunction "2_2") (pintype "passive"))
      (node (ref "T10") (pin "2") (pinfunction "S_2") (pintype "passive"))
      (node (ref "T15") (pin "2") (pinfunction "S_2") (pintype "passive"))
      (node (ref "T16") (pin "2") (pinfunction "S_2") (pintype "passive"))
      (node (ref "T5") (pin "2") (pinfunction "S_2") (pintype "passive"))
      (node (ref "T8") (pin "2") (pinfunction "S_2") (pintype "passive"))
      (node (ref "T9") (pin "2") (pinfunction "S_2") (pintype "passive"))
      (node (ref "U1") (pin "11") (pinfunction "ETPAD_11") (pintype "passive"))
      (node (ref "U1") (pin "9") (pinfunction "GND_9") (pintype "passive"))
      (node (ref "U2") (pin "4") (pinfunction "-V_4") (pintype "power_in"))
      (node (ref "U3") (pin "10") (pinfunction "GND_10") (pintype "power_in"))
      (node (ref "U3") (pin "18") (pinfunction "GND_18") (pintype "power_in"))
      (node (ref "U3") (pin "6") (pinfunction "GND_6") (pintype "power_in"))
      (node (ref "U4") (pin "2") (pinfunction "ADJ/GN_2") (pintype "power_in"))
      (node (ref "U4") (pin "4") (pintype "power_in"))
      (node (ref "U5") (pin "12") (pinfunction "VSSA_12") (pintype "passive"))
      (node (ref "U5") (pin "18") (pinfunction "VSS/PF4/PA3_18") (pintype "passive"))
      (node (ref "U5") (pin "31") (pinfunction "VSS/VCAP1_31") (pintype "passive"))
      (node (ref "U5") (pin "47") (pinfunction "VSS/VCAP2/PF6_47") (pintype "passive"))
      (node (ref "U5") (pin "63") (pinfunction "VSS_63") (pintype "passive"))
    )
    (net (code "41") (name "Net-(C17-Pad1)") (class "Default")
      (node (ref "C17") (pin "1") (pinfunction "1_1") (pintype "passive"))
      (node (ref "R18") (pin "1") (pinfunction "1_1") (pintype "passive"))
    )
    (net (code "42") (name "Net-(C45-Pad1)") (class "Default")
      (node (ref "C45") (pin "1") (pinfunction "1_1") (pintype "passive"))
      (node (ref "R65") (pin "1") (pinfunction "1_1") (pintype "passive"))
      (node (ref "R72") (pin "2") (pinfunction "2_2") (pintype "passive"))
    )
    (net (code "43") (name "Net-(C45-Pad2)") (class "Default")
      (node (ref "C45") (pin "2") (pinfunction "2_2") (pintype "passive"))
      (node (ref "J8") (pin "1") (pinfunction "1_1") (pintype "passive"))
      (node (ref "R72") (pin "1") (pinfunction "1_1") (pintype "passive"))
    )
    (net (code "44") (name "Net-(C47-Pad1)") (class "Default")
      (node (ref "C47") (pin "1") (pinfunction "1_1") (pintype "passive"))
      (node (ref "J8") (pin "2") (pinfunction "2_2") (pintype "passive"))
      (node (ref "R66") (pin "2") (pinfunction "2_2") (pintype "passive"))
    )
    (net (code "45") (name "Net-(D1-A)") (class "Default")
      (node (ref "C29") (pin "2") (pinfunction "2_2") (pintype "passive"))
      (node (ref "D1") (pin "1") (pinfunction "A_1") (pintype "passive"))
      (node (ref "J1") (pin "1") (pinfunction "1_1") (pintype "passive"))
      (node (ref "J2") (pin "1") (pinfunction "1_1") (pintype "passive"))
      (node (ref "R16") (pin "1") (pinfunction "1_1") (pintype "passive"))
      (node (ref "R26") (pin "2") (pinfunction "2_2") (pintype "passive"))
      (node (ref "R6") (pin "2") (pinfunction "2_2") (pintype "passive"))
      (node (ref "RV1") (pin "2") (pinfunction "2_2") (pintype "passive"))
      (node (ref "T14") (pin "4") (pinfunction "D_4") (pintype "passive"))
      (node (ref "T4") (pin "4") (pinfunction "D_4") (pintype "passive"))
      (node (ref "T7") (pin "4") (pinfunction "D_4") (pintype "passive"))
    )
    (net (code "46") (name "Net-(D2-K)") (class "Default")
      (node (ref "D2") (pin "2") (pinfunction "K_2") (pintype "passive"))
      (node (ref "R12") (pin "2") (pinfunction "2_2") (pintype "passive"))
    )
    (net (code "47") (name "Net-(D3-K)") (class "Default")
      (node (ref "D3") (pin "2") (pinfunction "K_2") (pintype "passive"))
      (node (ref "R15") (pin "2") (pinfunction "2_2") (pintype "passive"))
    )
    (net (code "48") (name "Net-(D4-K)") (class "Default")
      (node (ref "C6") (pin "2") (pinfunction "2_2") (pintype "passive"))
      (node (ref "D4") (pin "2") (pinfunction "K_2") (pintype "passive"))
      (node (ref "L1") (pin "1") (pinfunction "1_1") (pintype "passive"))
      (node (ref "U1") (pin "10") (pinfunction "PH_10") (pintype "passive"))
    )
    (net (code "49") (name "Net-(D5-K)") (class "Default")
      (node (ref "D5") (pin "2") (pinfunction "K_2") (pintype "passive"))
      (node (ref "D6") (pin "1") (pinfunction "A_1") (pintype "passive"))
    )
    (net (code "50") (name "Net-(D7-A)") (class "Default")
      (node (ref "C34") (pin "1") (pinfunction "1_1") (pintype "passive"))
      (node (ref "D7") (pin "1") (pinfunction "A_1") (pintype "passive"))
      (node (ref "D8") (pin "2") (pinfunction "K_2") (pintype "passive"))
    )
    (net (code "51") (name "Net-(D8-A)") (class "Default")
      (node (ref "D8") (pin "1") (pinfunction "A_1") (pintype "passive"))
      (node (ref "Q1") (pin "3") (pinfunction "D_3") (pintype "passive"))
    )
    (net (code "52") (name "Net-(D9-K)") (class "Default")
      (node (ref "D9") (pin "2") (pinfunction "K_2") (pintype "passive"))
      (node (ref "Q3") (pin "2") (pinfunction "S_2") (pintype "passive"))
      (node (ref "R69") (pin "1") (pinfunction "1_1") (pintype "passive"))
    )
    (net (code "53") (name "Net-(D10-A)") (class "Default")
      (node (ref "D10") (pin "1") (pinfunction "A_1") (pintype "passive"))
      (node (ref "R47") (pin "1") (pinfunction "1_1") (pintype "passive"))
    )
    (net (code "54") (name "Net-(D11-A)") (class "Default")
      (node (ref "D11") (pin "1") (pinfunction "A_1") (pintype "passive"))
      (node (ref "R49") (pin "1") (pinfunction "1_1") (pintype "passive"))
    )
    (net (code "55") (name "Net-(D12-A)") (class "Default")
      (node (ref "D12") (pin "1") (pinfunction "A_1") (pintype "passive"))
      (node (ref "R52") (pin "1") (pinfunction "1_1") (pintype "passive"))
    )
    (net (code "56") (name "Net-(D13-A)") (class "Default")
      (node (ref "D13") (pin "1") (pinfunction "A_1") (pintype "passive"))
      (node (ref "R54") (pin "1") (pinfunction "1_1") (pintype "passive"))
    )
    (net (code "57") (name "Net-(D14-A)") (class "Default")
      (node (ref "D14") (pin "1") (pinfunction "A_1") (pintype "passive"))
      (node (ref "J7") (pin "2") (pinfunction "2_2") (pintype "passive"))
      (node (ref "R57") (pin "2") (pinfunction "2_2") (pintype "passive"))
      (node (ref "R60") (pin "2") (pinfunction "2_2") (pintype "passive"))
      (node (ref "T11") (pin "2") (pinfunction "K_2") (pintype "passive"))
    )
    (net (code "58") (name "Net-(D14-K)") (class "Default")
      (node (ref "D14") (pin "2") (pinfunction "K_2") (pintype "passive"))
      (node (ref "R56") (pin "2") (pinfunction "2_2") (pintype "passive"))
      (node (ref "R57") (pin "1") (pinfunction "1_1") (pintype "passive"))
      (node (ref "R59") (pin "2") (pinfunction "2_2") (pintype "passive"))
      (node (ref "T11") (pin "1") (pinfunction "A_1") (pintype "passive"))
    )
    (net (code "59") (name "Net-(D15-K)") (class "Default")
      (node (ref "C2") (pin "2") (pinfunction "2_2") (pintype "passive"))
      (node (ref "C3") (pin "2") (pinfunction "2_2") (pintype "passive"))
      (node (ref "C43") (pin "2") (pinfunction "2_2") (pintype "passive"))
      (node (ref "C48") (pin "2") (pinfunction "2_2") (pintype "passive"))
      (node (ref "D15") (pin "2") (pinfunction "K_2") (pintype "passive"))
      (node (ref "D2") (pin "1") (pinfunction "A_1") (pintype "passive"))
      (node (ref "R4") (pin "2") (pinfunction "2_2") (pintype "passive"))
      (node (ref "R61") (pin "2") (pinfunction "2_2") (pintype "passive"))
      (node (ref "U1") (pin "2") (pinfunction "VIN_2") (pintype "passive"))
    )
    (net (code "60") (name "Net-(D16-A)") (class "Default")
      (node (ref "C44") (pin "1") (pinfunction "1_1") (pintype "passive"))
      (node (ref "D16") (pin "1") (pinfunction "A_1") (pintype "passive"))
      (node (ref "D17") (pin "2") (pinfunction "K_2") (pintype "passive"))
    )
    (net (code "61") (name "Net-(J3-Pad2)") (class "Default")
      (node (ref "J3") (pin "2") (pinfunction "2_2") (pintype "passive"))
      (node (ref "R10") (pin "2") (pinfunction "2_2") (pintype "passive"))
      (node (ref "R2") (pin "2") (pinfunction "2_2") (pintype "passive"))
      (node (ref "R3") (pin "1") (pinfunction "1_1") (pintype "passive"))
      (node (ref "R9") (pin "2") (pinfunction "2_2") (pintype "passive"))
      (node (ref "RV1") (pin "1") (pinfunction "1_1") (pintype "passive"))
    )
    (net (code "62") (name "Net-(J5-CLK)") (class "Default")
      (node (ref "J5") (pin "5") (pinfunction "CLK_5") (pintype "input"))
      (node (ref "U5") (pin "53") (pinfunction "SDMMC1_CK/USART3_CK/SPI3_MOSI/PC12_53") (pintype "passive"))
    )
    (net (code "63") (name "Net-(J5-DAT0)") (class "Default")
      (node (ref "J5") (pin "7") (pinfunction "DAT0_7") (pintype "bidirectional"))
      (node (ref "U5") (pin "39") (pinfunction "SDMMC1_D0/TSC_G4_IO3/PC8_39") (pintype "passive"))
    )
    (net (code "64") (name "Net-(J5-DAT1)") (class "Default")
      (node (ref "J5") (pin "8") (pinfunction "DAT1_8") (pintype "bidirectional"))
      (node (ref "U5") (pin "40") (pinfunction "SDMMC1_D1/TSC_G4_IO4/PC9_40") (pintype "passive"))
    )
    (net (code "65") (name "Net-(J5-DAT2)") (class "Default")
      (node (ref "J5") (pin "1") (pinfunction "DAT2_1") (pintype "bidirectional"))
      (node (ref "U5") (pin "51") (pinfunction "SDMMC1_D2/USART3_TX/SPI3_SCK/PC10_51") (pintype "passive"))
    )
    (net (code "66") (name "Net-(J5-DAT3{slash}CD)") (class "Default")
      (node (ref "J5") (pin "2") (pinfunction "DAT3/CD_2") (pintype "bidirectional"))
      (node (ref "U5") (pin "52") (pinfunction "SDMMC1_D3/USART3_RX/SPI3_MISO/PC11_52") (pintype "passive"))
    )
    (net (code "67") (name "Net-(J6-Pad1)") (class "Default")
      (node (ref "J6") (pin "1") (pinfunction "1_1") (pintype "passive"))
      (node (ref "R53") (pin "1") (pinfunction "1_1") (pintype "passive"))
    )
    (net (code "68") (name "Net-(J7-Pad1)") (class "Default")
      (node (ref "J7") (pin "1") (pinfunction "1_1") (pintype "passive"))
      (node (ref "R56") (pin "1") (pinfunction "1_1") (pintype "passive"))
    )
    (net (code "69") (name "Net-(Q1-G)") (class "Default")
      (node (ref "Q1") (pin "1") (pinfunction "G_1") (pintype "passive"))
      (node (ref "R35") (pin "2") (pinfunction "2_2") (pintype "passive"))
      (node (ref "R38") (pin "2") (pinfunction "2_2") (pintype "passive"))
    )
    (net (code "70") (name "Net-(Q3-G)") (class "Default")
      (node (ref "Q3") (pin "1") (pinfunction "G_1") (pintype "passive"))
      (node (ref "R69") (pin "2") (pinfunction "2_2") (pintype "passive"))
      (node (ref "R70") (pin "1") (pinfunction "1_1") (pintype "passive"))
    )
    (net (code "71") (name "Net-(R70-Pad2)") (class "Default")
      (node (ref "R70") (pin "2") (pinfunction "2_2") (pintype "passive"))
      (node (ref "R71") (pin "1") (pinfunction "1_1") (pintype "passive"))
    )
    (net (code "72") (name "Net-(T1-D)") (class "Default")
      (node (ref "C1") (pin "1") (pinfunction "1_1") (pintype "passive"))
      (node (ref "J1") (pin "2") (pinfunction "2_2") (pintype "passive"))
      (node (ref "R1") (pin "1") (pinfunction "1_1") (pintype "passive"))
      (node (ref "T1") (pin "4") (pinfunction "D_4") (pintype "passive"))
      (node (ref "T12") (pin "4") (pinfunction "D_4") (pintype "passive"))
      (node (ref "T2") (pin "4") (pinfunction "D_4") (pintype "passive"))
    )
    (net (code "73") (name "Net-(T1-S)") (class "Default")
      (node (ref "C1") (pin "2") (pinfunction "2_2") (pintype "passive"))
      (node (ref "R1") (pin "2") (pinfunction "2_2") (pintype "passive"))
      (node (ref "R17") (pin "2") (pinfunction "2_2") (pintype "passive"))
      (node (ref "R2") (pin "1") (pinfunction "1_1") (pintype "passive"))
      (node (ref "R8") (pin "2") (pinfunction "2_2") (pintype "passive"))
      (node (ref "T1") (pin "3") (pinfunction "S_3") (pintype "passive"))
      (node (ref "T12") (pin "3") (pinfunction "S_3") (pintype "passive"))
      (node (ref "T2") (pin "3") (pinfunction "S_3") (pintype "passive"))
    )
    (net (code "74") (name "Net-(T5-D)") (class "Default")
      (node (ref "R28") (pin "2") (pinfunction "2_2") (pintype "passive"))
      (node (ref "T5") (pin "3") (pinfunction "D_3") (pintype "passive"))
    )
    (net (code "75") (name "Net-(T8-D)") (class "Default")
      (node (ref "R33") (pin "2") (pinfunction "2_2") (pintype "passive"))
      (node (ref "T8") (pin "3") (pinfunction "D_3") (pintype "passive"))
    )
    (net (code "76") (name "Net-(T9-D)") (class "Default")
      (node (ref "C34") (pin "2") (pinfunction "2_2") (pintype "passive"))
      (node (ref "R36") (pin "2") (pinfunction "2_2") (pintype "passive"))
      (node (ref "T9") (pin "3") (pinfunction "D_3") (pintype "passive"))
    )
    (net (code "77") (name "Net-(T10-D)") (class "Default")
      (node (ref "R38") (pin "1") (pinfunction "1_1") (pintype "passive"))
      (node (ref "T10") (pin "3") (pinfunction "D_3") (pintype "passive"))
    )
    (net (code "78") (name "Net-(T11-C)") (class "Default")
      (node (ref "R55") (pin "2") (pinfunction "2_2") (pintype "passive"))
      (node (ref "R59") (pin "1") (pinfunction "1_1") (pintype "passive"))
      (node (ref "T11") (pin "4") (pinfunction "C_4") (pintype "passive"))
    )
    (net (code "79") (name "Net-(T15-D)") (class "Default")
      (node (ref "C44") (pin "2") (pinfunction "2_2") (pintype "passive"))
      (node (ref "R63") (pin "2") (pinfunction "2_2") (pintype "passive"))
      (node (ref "R65") (pin "2") (pinfunction "2_2") (pintype "passive"))
      (node (ref "T15") (pin "3") (pinfunction "D_3") (pintype "passive"))
    )
    (net (code "80") (name "Net-(T16-D)") (class "Default")
      (node (ref "R71") (pin "2") (pinfunction "2_2") (pintype "passive"))
      (node (ref "T16") (pin "3") (pinfunction "D_3") (pintype "passive"))
    )
    (net (code "81") (name "Net-(U1-BOOT)") (class "Default")
      (node (ref "C6") (pin "1") (pinfunction "1_1") (pintype "passive"))
      (node (ref "U1") (pin "1") (pinfunction "BOOT_1") (pintype "passive"))
    )
    (net (code "82") (name "Net-(U1-COMP)") (class "Default")
      (node (ref "C13") (pin "1") (pinfunction "1_1") (pintype "passive"))
      (node (ref "R18") (pin "2") (pinfunction "2_2") (pintype "passive"))
      (node (ref "U1") (pin "8") (pinfunction "COMP_8") (pintype "passive"))
    )
    (net (code "83") (name "Net-(U1-EN)") (class "Default")
      (node (ref "C7") (pin "1") (pinfunction "1_1") (pintype "passive"))
      (node (ref "R4") (pin "1") (pinfunction "1_1") (pintype "passive"))
      (node (ref "R7") (pin "2") (pinfunction "2_2") (pintype "passive"))
      (node (ref "U1") (pin "3") (pinfunction "EN_3") (pintype "passive"))
    )
    (net (code "84") (name "Net-(U1-RT{slash}CLK)") (class "Default")
      (node (ref "R21") (pin "2") (pinfunction "2_2") (pintype "passive"))
      (node (ref "U1") (pin "5") (pinfunction "RT/CLK_5") (pintype "passive"))
    )
    (net (code "85") (name "Net-(U1-SS{slash}TR)") (class "Default")
      (node (ref "C14") (pin "1") (pinfunction "1_1") (pintype "passive"))
      (node (ref "U1") (pin "4") (pinfunction "SS/TR_4") (pintype "passive"))
    )
    (net (code "86") (name "Net-(U1-VSENSE)") (class "Default")
      (node (ref "R13") (pin "2") (pinfunction "2_2") (pintype "passive"))
      (node (ref "R5") (pin "1") (pinfunction "1_1") (pintype "passive"))
      (node (ref "U1") (pin "7") (pinfunction "VSENSE_7") (pintype "passive"))
    )
    (net (code "87") (name "Net-(U2A-+)") (class "Default")
      (node (ref "C16") (pin "2") (pinfunction "2_2") (pintype "passive"))
      (node (ref "C21") (pin "1") (pinfunction "1_1") (pintype "passive"))
      (node (ref "R10") (pin "1") (pinfunction "1_1") (pintype "passive"))
      (node (ref "U2") (pin "3") (pinfunction "+_3") (pintype "input"))
    )
    (net (code "88") (name "Net-(U2A-+V)") (class "Default")
      (node (ref "C10") (pin "1") (pinfunction "1_1") (pintype "passive"))
      (node (ref "C11") (pin "2") (pinfunction "2_2") (pintype "passive"))
      (node (ref "L2") (pin "2") (pinfunction "2_2") (pintype "passive"))
      (node (ref "L3") (pin "2") (pinfunction "2_2") (pintype "passive"))
      (node (ref "U2") (pin "8") (pinfunction "+V_8") (pintype "power_in"))
    )
    (net (code "89") (name "Net-(U2A--)") (class "Default")
      (node (ref "C16") (pin "1") (pinfunction "1_1") (pintype "passive"))
      (node (ref "C19") (pin "1") (pinfunction "1_1") (pintype "passive"))
      (node (ref "R11") (pin "1") (pinfunction "1_1") (pintype "passive"))
      (node (ref "R23") (pin "2") (pinfunction "2_2") (pintype "passive"))
      (node (ref "U2") (pin "2") (pinfunction "-_2") (pintype "input"))
    )
    (net (code "90") (name "Net-(U2A-O)") (class "Default")
      (node (ref "R20") (pin "1") (pinfunction "1_1") (pintype "passive"))
      (node (ref "R23") (pin "1") (pinfunction "1_1") (pintype "passive"))
      (node (ref "U2") (pin "1") (pinfunction "O_1") (pintype "output"))
    )
    (net (code "91") (name "Net-(U2B-+)") (class "Default")
      (node (ref "C15") (pin "2") (pinfunction "2_2") (pintype "passive"))
      (node (ref "C20") (pin "1") (pinfunction "1_1") (pintype "passive"))
      (node (ref "R8") (pin "1") (pinfunction "1_1") (pintype "passive"))
      (node (ref "U2") (pin "5") (pinfunction "+_5") (pintype "input"))
    )
    (net (code "92") (name "Net-(U2B--)") (class "Default")
      (node (ref "C15") (pin "1") (pinfunction "1_1") (pintype "passive"))
      (node (ref "C18") (pin "1") (pinfunction "1_1") (pintype "passive"))
      (node (ref "R22") (pin "2") (pinfunction "2_2") (pintype "passive"))
      (node (ref "R9") (pin "1") (pinfunction "1_1") (pintype "passive"))
      (node (ref "U2") (pin "6") (pinfunction "-_6") (pintype "input"))
    )
    (net (code "93") (name "Net-(U2B-O)") (class "Default")
      (node (ref "R19") (pin "1") (pinfunction "1_1") (pintype "passive"))
      (node (ref "R22") (pin "1") (pinfunction "1_1") (pintype "passive"))
      (node (ref "U2") (pin "7") (pinfunction "O_7") (pintype "output"))
    )
    (net (code "94") (name "Net-(U3-EN{slash}CH_PD)") (class "Default")
      (node (ref "R27") (pin "2") (pinfunction "2_2") (pintype "passive"))
      (node (ref "U3") (pin "14") (pinfunction "EN/CH_PD_14") (pintype "input"))
    )
    (net (code "95") (name "Net-(U3-IO0)") (class "Default")
      (node (ref "R24") (pin "1") (pinfunction "1_1") (pintype "passive"))
      (node (ref "U3") (pin "3") (pinfunction "IO0_3") (pintype "bidirectional"))
    )
    (net (code "96") (name "Net-(U3-RSTB)") (class "Default")
      (node (ref "C32") (pin "1") (pinfunction "1_1") (pintype "passive"))
      (node (ref "R29") (pin "2") (pinfunction "2_2") (pintype "passive"))
      (node (ref "U3") (pin "12") (pinfunction "RSTB_12") (pintype "input"))
    )
    (net (code "97") (name "Net-(U5A-PA9{slash}TIM1_CH2{slash}I2C1_SCL{slash}USART1_TX{slash}TIM15_BKIN)") (class "Default")
      (node (ref "R41") (pin "2") (pinfunction "2_2") (pintype "passive"))
      (node (ref "U5") (pin "42") (pinfunction "PA9/TIM1_CH2/I2C1_SCL/USART1_TX/TIM15_BKIN_42") (pintype "passive"))
    )
    (net (code "98") (name "Net-(U5A-PA10{slash}TIM1_CH3{slash}I2C1_SDA{slash}USART1_RX{slash})") (class "Default")
      (node (ref "R42") (pin "2") (pinfunction "2_2") (pintype "passive"))
      (node (ref "U5") (pin "43") (pinfunction "PA10/TIM1_CH3/I2C1_SDA/USART1_RX/_43") (pintype "passive"))
    )
    (net (code "99") (name "Net-(U5B-BOOT0{slash}PH3)") (class "Default")
      (node (ref "R50") (pin "2") (pinfunction "2_2") (pintype "passive"))
      (node (ref "R51") (pin "2") (pinfunction "2_2") (pintype "passive"))
      (node (ref "U5") (pin "60") (pinfunction "BOOT0/PH3_60") (pintype "passive"))
    )
    (net (code "100") (name "Net-(U5B-PF0{slash}PD0{slash}PH0_-_OSC_IN)") (class "Default")
      (node (ref "C37") (pin "2") (pinfunction "2_2") (pintype "passive"))
      (node (ref "U5") (pin "5") (pinfunction "PF0/PD0/PH0_-_OSC_IN_5") (pintype "passive"))
      (node (ref "X1") (pin "2") (pinfunction "2_2") (pintype "passive"))
    )
    (net (code "101") (name "Net-(U5B-PF1{slash}PD1{slash}PH1_-_OSC_OUT)") (class "Default")
      (node (ref "C36") (pin "2") (pinfunction "2_2") (pintype "passive"))
      (node (ref "U5") (pin "6") (pinfunction "PF1/PD1/PH1_-_OSC_OUT_6") (pintype "passive"))
      (node (ref "X1") (pin "1") (pinfunction "1_1") (pintype "passive"))
    )
    (net (code "102") (name "SMPS") (class "Default")
      (node (ref "D1") (pin "2") (pinfunction "K_2") (pintype "passive"))
      (node (ref "Q3") (pin "3") (pinfunction "D_3") (pintype "passive"))
      (node (ref "R61") (pin "1") (pinfunction "1_1") (pintype "passive"))
    )
    (net (code "103") (name "VBAT") (class "Default")
      (node (ref "C28") (pin "1") (pinfunction "1_1") (pintype "passive"))
      (node (ref "D9") (pin "1") (pinfunction "A_1") (pintype "passive"))
      (node (ref "J3") (pin "1") (pinfunction "1_1") (pintype "passive"))
      (node (ref "R25") (pin "1") (pinfunction "1_1") (pintype "passive"))
      (node (ref "R37") (pin "2") (pinfunction "2_2") (pintype "passive"))
      (node (ref "T13") (pin "4") (pinfunction "D_4") (pintype "passive"))
      (node (ref "T3") (pin "4") (pinfunction "D_4") (pintype "passive"))
      (node (ref "T6") (pin "4") (pinfunction "D_4") (pintype "passive"))
    )
    (net (code "104") (name "unconnected-(U1-PWRGD-Pad6)") (class "Default")
      (node (ref "U1") (pin "6") (pinfunction "PWRGD_6") (pintype "passive"))
    )
    (net (code "105") (name "unconnected-(U3-IO2{slash}U1TXD{slash}SDA-Pad4)") (class "Default")
      (node (ref "U3") (pin "4") (pinfunction "IO2/U1TXD/SDA_4") (pintype "bidirectional"))
    )
    (net (code "106") (name "unconnected-(U3-IO4-Pad2)") (class "Default")
      (node (ref "U3") (pin "2") (pinfunction "IO4_2") (pintype "bidirectional"))
    )
    (net (code "107") (name "unconnected-(U3-IO5-Pad8)") (class "Default")
      (node (ref "U3") (pin "8") (pinfunction "IO5_8") (pintype "bidirectional"))
    )
    (net (code "108") (name "unconnected-(U3-IO12{slash}MISO{slash}PWM0-Pad16)") (class "Default")
      (node (ref "U3") (pin "16") (pinfunction "IO12/MISO/PWM0_16") (pintype "bidirectional"))
    )
    (net (code "109") (name "unconnected-(U3-IO13{slash}MOSI{slash}-Pad7)") (class "Default")
      (node (ref "U3") (pin "7") (pinfunction "IO13/MOSI/_7") (pintype "bidirectional"))
    )
    (net (code "110") (name "unconnected-(U3-IO14{slash}CLK{slash}SCL{slash}PWM2-Pad17)") (class "Default")
      (node (ref "U3") (pin "17") (pinfunction "IO14/CLK/SCL/PWM2_17") (pintype "bidirectional"))
    )
    (net (code "111") (name "unconnected-(U3-IO15{slash}MIDO{slash}U0RTS{slash}PWM1-Pad5)") (class "Default")
      (node (ref "U3") (pin "5") (pinfunction "IO15/MIDO/U0RTS/PWM1_5") (pintype "bidirectional"))
    )
    (net (code "112") (name "unconnected-(U3-IO16{slash}WKUP-Pad15)") (class "Default")
      (node (ref "U3") (pin "15") (pinfunction "IO16/WKUP_15") (pintype "passive"))
    )
    (net (code "113") (name "unconnected-(U3-TOUT-Pad13)") (class "Default")
      (node (ref "U3") (pin "13") (pinfunction "TOUT_13") (pintype "input+no_connect"))
    )
    (net (code "114") (name "unconnected-(U5A-COMP2_INP{slash}SPI1_MISO{slash}I2C3_SDA{slash}NJTRST{slash}PB4-Pad56)") (class "Default")
      (node (ref "U5") (pin "56") (pinfunction "COMP2_INP/SPI1_MISO/I2C3_SDA/NJTRST/PB4_56") (pintype "passive"))
    )
    (net (code "115") (name "unconnected-(U5A-PA11{slash}TIM1_CH4{slash}SPI1_MISO{slash}CAN1_RX-Pad44)") (class "Default")
      (node (ref "U5") (pin "44") (pinfunction "PA11/TIM1_CH4/SPI1_MISO/CAN1_RX_44") (pintype "passive"))
    )
    (net (code "116") (name "unconnected-(U5A-PA12{slash}SPI1_MOSI{slash}CAN1_TX{slash}TIM1_ETR{slash}U1_485_DIR-Pad45)") (class "Default")
      (node (ref "U5") (pin "45") (pinfunction "PA12/SPI1_MOSI/CAN1_TX/TIM1_ETR/U1_485_DIR_45") (pintype "passive"))
    )
    (net (code "117") (name "unconnected-(U5A-PA15{slash}JTDI{slash}TIM2_CH1{slash}USART2_RX{slash}SPI1_NSS{slash}SPI3_NSS-Pad50)") (class "Default")
      (node (ref "U5") (pin "50") (pinfunction "PA15/JTDI/TIM2_CH1/USART2_RX/SPI1_NSS/SPI3_NSS_50") (pintype "passive"))
    )
    (net (code "118") (name "unconnected-(U5A-PC6{slash}TSC_G4_IO1{slash}SDMMC1_D6-Pad37)") (class "Default")
      (node (ref "U5") (pin "37") (pinfunction "PC6/TSC_G4_IO1/SDMMC1_D6_37") (pintype "passive"))
    )
    (net (code "119") (name "unconnected-(U5A-PC7{slash}TSC_G4_IO2{slash}SDMMC1_D7-Pad38)") (class "Default")
      (node (ref "U5") (pin "38") (pinfunction "PC7/TSC_G4_IO2/SDMMC1_D7_38") (pintype "passive"))
    )
    (net (code "120") (name "unconnected-(U5A-PC14_-_OSC32_IN-Pad3)") (class "Default")
      (node (ref "U5") (pin "3") (pinfunction "PC14_-_OSC32_IN_3") (pintype "passive"))
    )
    (net (code "121") (name "unconnected-(U5A-PC15_-_OSC32_OUT-Pad4)") (class "Default")
      (node (ref "U5") (pin "4") (pinfunction "PC15_-_OSC32_OUT_4") (pintype "passive"))
    )
    (net (code "122") (name "unconnected-(U5A-PVD_IN{slash}USART1_RX{slash}I2C1_SDA{slash}LPTIM1_IN2{slash}PB7-Pad59)") (class "Default")
      (node (ref "U5") (pin "59") (pinfunction "PVD_IN/USART1_RX/I2C1_SDA/LPTIM1_IN2/PB7_59") (pintype "passive"))
    )
    (net (code "123") (name "unconnected-(U5A-RTC_TAMP1{slash}WKUP2{slash}PC13{slash}RTC_OUT-Pad2)") (class "Default")
      (node (ref "U5") (pin "2") (pinfunction "RTC_TAMP1/WKUP2/PC13/RTC_OUT_2") (pintype "passive"))
    )
    (net (code "124") (name "unconnected-(U5A-TIM16_CH1N{slash}USART1_TX{slash}I2C1_SCL{slash}LPTIM1_ETR{slash}PB6-Pad58)") (class "Default")
      (node (ref "U5") (pin "58") (pinfunction "TIM16_CH1N/USART1_TX/I2C1_SCL/LPTIM1_ETR/PB6_58") (pintype "passive"))
    )
    (net (code "125") (name "unconnected-(U5A-USART1_CK{slash}SPI1_MOSI{slash}I2C1_SMBA{slash}LPTIM1_IN1{slash}PB5-Pad57)") (class "Default")
      (node (ref "U5") (pin "57") (pinfunction "USART1_CK/SPI1_MOSI/I2C1_SMBA/LPTIM1_IN1/PB5_57") (pintype "passive"))
    )
  )
)
